# Sheet_1_2026-02-10.net
KiCad netlist of a schematic drawn in Altium Designer
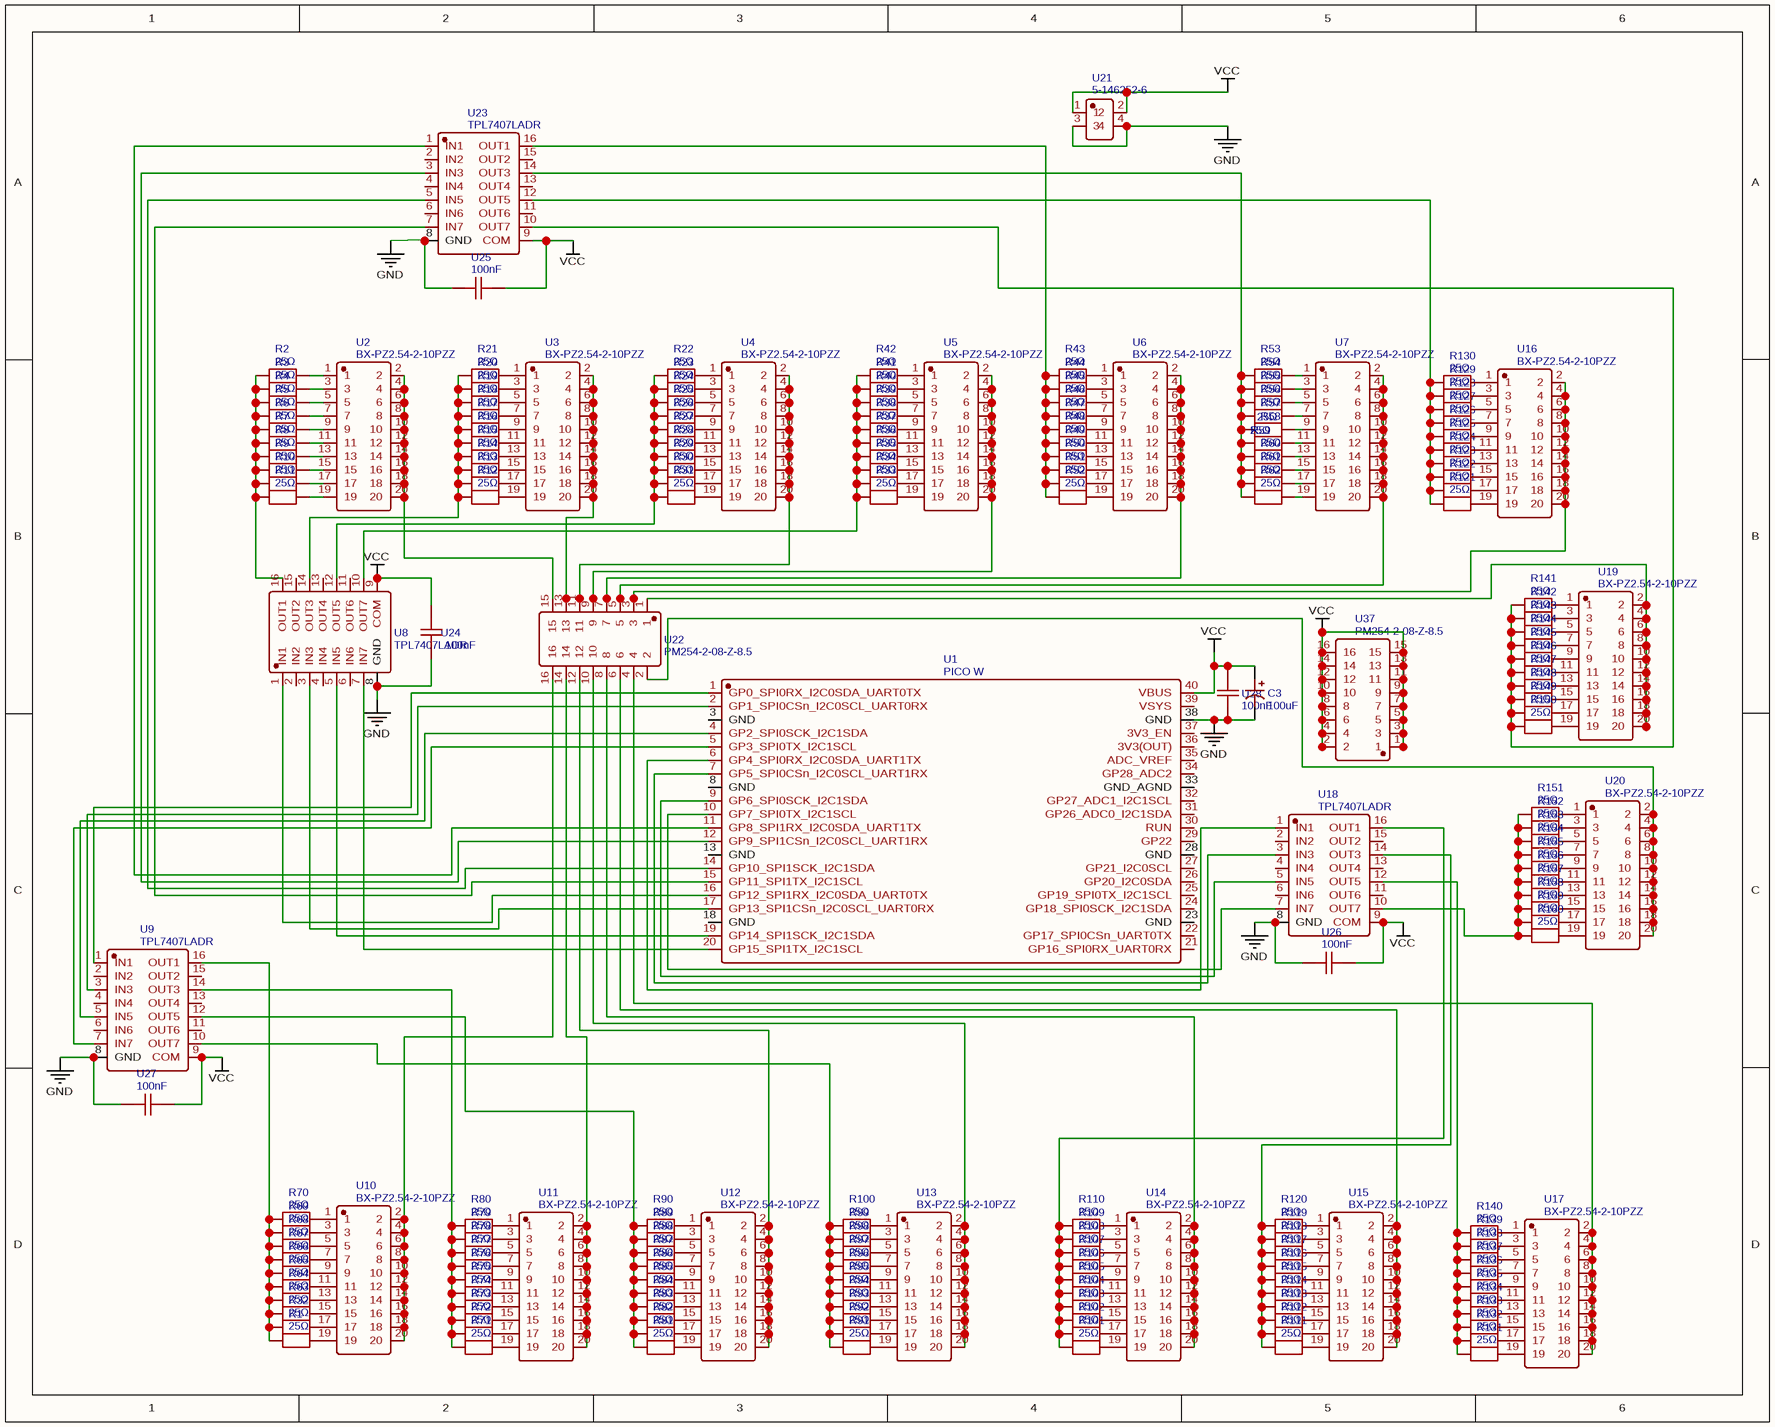
[diagram p0: Sheet_1_2026-02-10.schdoc]

(export (version "E")
  (design (tool "Eeschema 10.0.6"))
  (components
    (comp (ref "C3")
      (value "100uF")
      (fields
        (field (name "MANUFACTURER") "Econd(米朗电子)")
        (field (name "MANUFACTURER PART") "100uF25V6.3x11KM")
        (field (name "CONTRIBUTOR") "lcsc")
      )
      (libsource (lib "altium-import") (part "root_3_100uF_"))
    )
    (comp (ref "R1")
      (value "25Ω")
      (fields
        (field (name "MANUFACTURER") "YAGEO(国巨)")
        (field (name "MANUFACTURER PART") "RT0805BRD0725RL")
        (field (name "CONTRIBUTOR") "lcsc")
      )
      (libsource (lib "altium-import") (part "root_0_25Ω_"))
    )
    (comp (ref "R2")
      (value "25Ω")
      (fields
        (field (name "MANUFACTURER") "YAGEO(国巨)")
        (field (name "MANUFACTURER PART") "RT0805BRD0725RL")
        (field (name "CONTRIBUTOR") "lcsc")
      )
      (libsource (lib "altium-import") (part "root_0_25Ω_"))
    )
    (comp (ref "R3")
      (value "25Ω")
      (fields
        (field (name "MANUFACTURER") "YAGEO(国巨)")
        (field (name "MANUFACTURER PART") "RT0805BRD0725RL")
        (field (name "CONTRIBUTOR") "lcsc")
      )
      (libsource (lib "altium-import") (part "root_0_25Ω_"))
    )
    (comp (ref "R4")
      (value "25Ω")
      (fields
        (field (name "MANUFACTURER") "YAGEO(国巨)")
        (field (name "MANUFACTURER PART") "RT0805BRD0725RL")
        (field (name "CONTRIBUTOR") "lcsc")
      )
      (libsource (lib "altium-import") (part "root_0_25Ω_"))
    )
    (comp (ref "R5")
      (value "25Ω")
      (fields
        (field (name "MANUFACTURER") "YAGEO(国巨)")
        (field (name "MANUFACTURER PART") "RT0805BRD0725RL")
        (field (name "CONTRIBUTOR") "lcsc")
      )
      (libsource (lib "altium-import") (part "root_0_25Ω_"))
    )
    (comp (ref "R6")
      (value "25Ω")
      (fields
        (field (name "MANUFACTURER") "YAGEO(国巨)")
        (field (name "MANUFACTURER PART") "RT0805BRD0725RL")
        (field (name "CONTRIBUTOR") "lcsc")
      )
      (libsource (lib "altium-import") (part "root_0_25Ω_"))
    )
    (comp (ref "R7")
      (value "25Ω")
      (fields
        (field (name "MANUFACTURER") "YAGEO(国巨)")
        (field (name "MANUFACTURER PART") "RT0805BRD0725RL")
        (field (name "CONTRIBUTOR") "lcsc")
      )
      (libsource (lib "altium-import") (part "root_0_25Ω_"))
    )
    (comp (ref "R8")
      (value "25Ω")
      (fields
        (field (name "MANUFACTURER") "YAGEO(国巨)")
        (field (name "MANUFACTURER PART") "RT0805BRD0725RL")
        (field (name "CONTRIBUTOR") "lcsc")
      )
      (libsource (lib "altium-import") (part "root_0_25Ω_"))
    )
    (comp (ref "R9")
      (value "25Ω")
      (fields
        (field (name "MANUFACTURER") "YAGEO(国巨)")
        (field (name "MANUFACTURER PART") "RT0805BRD0725RL")
        (field (name "CONTRIBUTOR") "lcsc")
      )
      (libsource (lib "altium-import") (part "root_0_25Ω_"))
    )
    (comp (ref "R10")
      (value "25Ω")
      (fields
        (field (name "MANUFACTURER") "YAGEO(国巨)")
        (field (name "MANUFACTURER PART") "RT0805BRD0725RL")
        (field (name "CONTRIBUTOR") "lcsc")
      )
      (libsource (lib "altium-import") (part "root_0_25Ω_"))
    )
    (comp (ref "R11")
      (value "25Ω")
      (fields
        (field (name "MANUFACTURER") "YAGEO(国巨)")
        (field (name "MANUFACTURER PART") "RT0805BRD0725RL")
        (field (name "CONTRIBUTOR") "lcsc")
      )
      (libsource (lib "altium-import") (part "root_0_25Ω_"))
    )
    (comp (ref "R12")
      (value "25Ω")
      (fields
        (field (name "MANUFACTURER") "YAGEO(国巨)")
        (field (name "MANUFACTURER PART") "RT0805BRD0725RL")
        (field (name "CONTRIBUTOR") "lcsc")
      )
      (libsource (lib "altium-import") (part "root_0_25Ω_"))
    )
    (comp (ref "R13")
      (value "25Ω")
      (fields
        (field (name "MANUFACTURER") "YAGEO(国巨)")
        (field (name "MANUFACTURER PART") "RT0805BRD0725RL")
        (field (name "CONTRIBUTOR") "lcsc")
      )
      (libsource (lib "altium-import") (part "root_0_25Ω_"))
    )
    (comp (ref "R14")
      (value "25Ω")
      (fields
        (field (name "MANUFACTURER") "YAGEO(国巨)")
        (field (name "MANUFACTURER PART") "RT0805BRD0725RL")
        (field (name "CONTRIBUTOR") "lcsc")
      )
      (libsource (lib "altium-import") (part "root_0_25Ω_"))
    )
    (comp (ref "R15")
      (value "25Ω")
      (fields
        (field (name "MANUFACTURER") "YAGEO(国巨)")
        (field (name "MANUFACTURER PART") "RT0805BRD0725RL")
        (field (name "CONTRIBUTOR") "lcsc")
      )
      (libsource (lib "altium-import") (part "root_0_25Ω_"))
    )
    (comp (ref "R16")
      (value "25Ω")
      (fields
        (field (name "MANUFACTURER") "YAGEO(国巨)")
        (field (name "MANUFACTURER PART") "RT0805BRD0725RL")
        (field (name "CONTRIBUTOR") "lcsc")
      )
      (libsource (lib "altium-import") (part "root_0_25Ω_"))
    )
    (comp (ref "R17")
      (value "25Ω")
      (fields
        (field (name "MANUFACTURER") "YAGEO(国巨)")
        (field (name "MANUFACTURER PART") "RT0805BRD0725RL")
        (field (name "CONTRIBUTOR") "lcsc")
      )
      (libsource (lib "altium-import") (part "root_0_25Ω_"))
    )
    (comp (ref "R18")
      (value "25Ω")
      (fields
        (field (name "MANUFACTURER") "YAGEO(国巨)")
        (field (name "MANUFACTURER PART") "RT0805BRD0725RL")
        (field (name "CONTRIBUTOR") "lcsc")
      )
      (libsource (lib "altium-import") (part "root_0_25Ω_"))
    )
    (comp (ref "R19")
      (value "25Ω")
      (fields
        (field (name "MANUFACTURER") "YAGEO(国巨)")
        (field (name "MANUFACTURER PART") "RT0805BRD0725RL")
        (field (name "CONTRIBUTOR") "lcsc")
      )
      (libsource (lib "altium-import") (part "root_0_25Ω_"))
    )
    (comp (ref "R20")
      (value "25Ω")
      (fields
        (field (name "MANUFACTURER") "YAGEO(国巨)")
        (field (name "MANUFACTURER PART") "RT0805BRD0725RL")
        (field (name "CONTRIBUTOR") "lcsc")
      )
      (libsource (lib "altium-import") (part "root_0_25Ω_"))
    )
    (comp (ref "R21")
      (value "25Ω")
      (fields
        (field (name "MANUFACTURER") "YAGEO(国巨)")
        (field (name "MANUFACTURER PART") "RT0805BRD0725RL")
        (field (name "CONTRIBUTOR") "lcsc")
      )
      (libsource (lib "altium-import") (part "root_0_25Ω_"))
    )
    (comp (ref "R22")
      (value "25Ω")
      (fields
        (field (name "MANUFACTURER") "YAGEO(国巨)")
        (field (name "MANUFACTURER PART") "RT0805BRD0725RL")
        (field (name "CONTRIBUTOR") "lcsc")
      )
      (libsource (lib "altium-import") (part "root_0_25Ω_"))
    )
    (comp (ref "R23")
      (value "25Ω")
      (fields
        (field (name "MANUFACTURER") "YAGEO(国巨)")
        (field (name "MANUFACTURER PART") "RT0805BRD0725RL")
        (field (name "CONTRIBUTOR") "lcsc")
      )
      (libsource (lib "altium-import") (part "root_0_25Ω_"))
    )
    (comp (ref "R24")
      (value "25Ω")
      (fields
        (field (name "MANUFACTURER") "YAGEO(国巨)")
        (field (name "MANUFACTURER PART") "RT0805BRD0725RL")
        (field (name "CONTRIBUTOR") "lcsc")
      )
      (libsource (lib "altium-import") (part "root_0_25Ω_"))
    )
    (comp (ref "R25")
      (value "25Ω")
      (fields
        (field (name "MANUFACTURER") "YAGEO(国巨)")
        (field (name "MANUFACTURER PART") "RT0805BRD0725RL")
        (field (name "CONTRIBUTOR") "lcsc")
      )
      (libsource (lib "altium-import") (part "root_0_25Ω_"))
    )
    (comp (ref "R26")
      (value "25Ω")
      (fields
        (field (name "MANUFACTURER") "YAGEO(国巨)")
        (field (name "MANUFACTURER PART") "RT0805BRD0725RL")
        (field (name "CONTRIBUTOR") "lcsc")
      )
      (libsource (lib "altium-import") (part "root_0_25Ω_"))
    )
    (comp (ref "R27")
      (value "25Ω")
      (fields
        (field (name "MANUFACTURER") "YAGEO(国巨)")
        (field (name "MANUFACTURER PART") "RT0805BRD0725RL")
        (field (name "CONTRIBUTOR") "lcsc")
      )
      (libsource (lib "altium-import") (part "root_0_25Ω_"))
    )
    (comp (ref "R28")
      (value "25Ω")
      (fields
        (field (name "MANUFACTURER") "YAGEO(国巨)")
        (field (name "MANUFACTURER PART") "RT0805BRD0725RL")
        (field (name "CONTRIBUTOR") "lcsc")
      )
      (libsource (lib "altium-import") (part "root_0_25Ω_"))
    )
    (comp (ref "R29")
      (value "25Ω")
      (fields
        (field (name "MANUFACTURER") "YAGEO(国巨)")
        (field (name "MANUFACTURER PART") "RT0805BRD0725RL")
        (field (name "CONTRIBUTOR") "lcsc")
      )
      (libsource (lib "altium-import") (part "root_0_25Ω_"))
    )
    (comp (ref "R30")
      (value "25Ω")
      (fields
        (field (name "MANUFACTURER") "YAGEO(国巨)")
        (field (name "MANUFACTURER PART") "RT0805BRD0725RL")
        (field (name "CONTRIBUTOR") "lcsc")
      )
      (libsource (lib "altium-import") (part "root_0_25Ω_"))
    )
    (comp (ref "R31")
      (value "25Ω")
      (fields
        (field (name "MANUFACTURER") "YAGEO(国巨)")
        (field (name "MANUFACTURER PART") "RT0805BRD0725RL")
        (field (name "CONTRIBUTOR") "lcsc")
      )
      (libsource (lib "altium-import") (part "root_0_25Ω_"))
    )
    (comp (ref "R32")
      (value "25Ω")
      (fields
        (field (name "MANUFACTURER") "YAGEO(国巨)")
        (field (name "MANUFACTURER PART") "RT0805BRD0725RL")
        (field (name "CONTRIBUTOR") "lcsc")
      )
      (libsource (lib "altium-import") (part "root_0_25Ω_"))
    )
    (comp (ref "R33")
      (value "25Ω")
      (fields
        (field (name "MANUFACTURER") "YAGEO(国巨)")
        (field (name "MANUFACTURER PART") "RT0805BRD0725RL")
        (field (name "CONTRIBUTOR") "lcsc")
      )
      (libsource (lib "altium-import") (part "root_0_25Ω_"))
    )
    (comp (ref "R34")
      (value "25Ω")
      (fields
        (field (name "MANUFACTURER") "YAGEO(国巨)")
        (field (name "MANUFACTURER PART") "RT0805BRD0725RL")
        (field (name "CONTRIBUTOR") "lcsc")
      )
      (libsource (lib "altium-import") (part "root_0_25Ω_"))
    )
    (comp (ref "R35")
      (value "25Ω")
      (fields
        (field (name "MANUFACTURER") "YAGEO(国巨)")
        (field (name "MANUFACTURER PART") "RT0805BRD0725RL")
        (field (name "CONTRIBUTOR") "lcsc")
      )
      (libsource (lib "altium-import") (part "root_0_25Ω_"))
    )
    (comp (ref "R36")
      (value "25Ω")
      (fields
        (field (name "MANUFACTURER") "YAGEO(国巨)")
        (field (name "MANUFACTURER PART") "RT0805BRD0725RL")
        (field (name "CONTRIBUTOR") "lcsc")
      )
      (libsource (lib "altium-import") (part "root_0_25Ω_"))
    )
    (comp (ref "R37")
      (value "25Ω")
      (fields
        (field (name "MANUFACTURER") "YAGEO(国巨)")
        (field (name "MANUFACTURER PART") "RT0805BRD0725RL")
        (field (name "CONTRIBUTOR") "lcsc")
      )
      (libsource (lib "altium-import") (part "root_0_25Ω_"))
    )
    (comp (ref "R38")
      (value "25Ω")
      (fields
        (field (name "MANUFACTURER") "YAGEO(国巨)")
        (field (name "MANUFACTURER PART") "RT0805BRD0725RL")
        (field (name "CONTRIBUTOR") "lcsc")
      )
      (libsource (lib "altium-import") (part "root_0_25Ω_"))
    )
    (comp (ref "R39")
      (value "25Ω")
      (fields
        (field (name "MANUFACTURER") "YAGEO(国巨)")
        (field (name "MANUFACTURER PART") "RT0805BRD0725RL")
        (field (name "CONTRIBUTOR") "lcsc")
      )
      (libsource (lib "altium-import") (part "root_0_25Ω_"))
    )
    (comp (ref "R40")
      (value "25Ω")
      (fields
        (field (name "MANUFACTURER") "YAGEO(国巨)")
        (field (name "MANUFACTURER PART") "RT0805BRD0725RL")
        (field (name "CONTRIBUTOR") "lcsc")
      )
      (libsource (lib "altium-import") (part "root_0_25Ω_"))
    )
    (comp (ref "R41")
      (value "25Ω")
      (fields
        (field (name "MANUFACTURER") "YAGEO(国巨)")
        (field (name "MANUFACTURER PART") "RT0805BRD0725RL")
        (field (name "CONTRIBUTOR") "lcsc")
      )
      (libsource (lib "altium-import") (part "root_0_25Ω_"))
    )
    (comp (ref "R42")
      (value "25Ω")
      (fields
        (field (name "MANUFACTURER") "YAGEO(国巨)")
        (field (name "MANUFACTURER PART") "RT0805BRD0725RL")
        (field (name "CONTRIBUTOR") "lcsc")
      )
      (libsource (lib "altium-import") (part "root_0_25Ω_"))
    )
    (comp (ref "R43")
      (value "25Ω")
      (fields
        (field (name "MANUFACTURER") "YAGEO(国巨)")
        (field (name "MANUFACTURER PART") "RT0805BRD0725RL")
        (field (name "CONTRIBUTOR") "lcsc")
      )
      (libsource (lib "altium-import") (part "root_0_25Ω_"))
    )
    (comp (ref "R44")
      (value "25Ω")
      (fields
        (field (name "MANUFACTURER") "YAGEO(国巨)")
        (field (name "MANUFACTURER PART") "RT0805BRD0725RL")
        (field (name "CONTRIBUTOR") "lcsc")
      )
      (libsource (lib "altium-import") (part "root_0_25Ω_"))
    )
    (comp (ref "R45")
      (value "25Ω")
      (fields
        (field (name "MANUFACTURER") "YAGEO(国巨)")
        (field (name "MANUFACTURER PART") "RT0805BRD0725RL")
        (field (name "CONTRIBUTOR") "lcsc")
      )
      (libsource (lib "altium-import") (part "root_0_25Ω_"))
    )
    (comp (ref "R46")
      (value "25Ω")
      (fields
        (field (name "MANUFACTURER") "YAGEO(国巨)")
        (field (name "MANUFACTURER PART") "RT0805BRD0725RL")
        (field (name "CONTRIBUTOR") "lcsc")
      )
      (libsource (lib "altium-import") (part "root_0_25Ω_"))
    )
    (comp (ref "R47")
      (value "25Ω")
      (fields
        (field (name "MANUFACTURER") "YAGEO(国巨)")
        (field (name "MANUFACTURER PART") "RT0805BRD0725RL")
        (field (name "CONTRIBUTOR") "lcsc")
      )
      (libsource (lib "altium-import") (part "root_0_25Ω_"))
    )
    (comp (ref "R48")
      (value "25Ω")
      (fields
        (field (name "MANUFACTURER") "YAGEO(国巨)")
        (field (name "MANUFACTURER PART") "RT0805BRD0725RL")
        (field (name "CONTRIBUTOR") "lcsc")
      )
      (libsource (lib "altium-import") (part "root_0_25Ω_"))
    )
    (comp (ref "R49")
      (value "25Ω")
      (fields
        (field (name "MANUFACTURER") "YAGEO(国巨)")
        (field (name "MANUFACTURER PART") "RT0805BRD0725RL")
        (field (name "CONTRIBUTOR") "lcsc")
      )
      (libsource (lib "altium-import") (part "root_0_25Ω_"))
    )
    (comp (ref "R50")
      (value "25Ω")
      (fields
        (field (name "MANUFACTURER") "YAGEO(国巨)")
        (field (name "MANUFACTURER PART") "RT0805BRD0725RL")
        (field (name "CONTRIBUTOR") "lcsc")
      )
      (libsource (lib "altium-import") (part "root_0_25Ω_"))
    )
    (comp (ref "R51")
      (value "25Ω")
      (fields
        (field (name "MANUFACTURER") "YAGEO(国巨)")
        (field (name "MANUFACTURER PART") "RT0805BRD0725RL")
        (field (name "CONTRIBUTOR") "lcsc")
      )
      (libsource (lib "altium-import") (part "root_0_25Ω_"))
    )
    (comp (ref "R52")
      (value "25Ω")
      (fields
        (field (name "MANUFACTURER") "YAGEO(国巨)")
        (field (name "MANUFACTURER PART") "RT0805BRD0725RL")
        (field (name "CONTRIBUTOR") "lcsc")
      )
      (libsource (lib "altium-import") (part "root_0_25Ω_"))
    )
    (comp (ref "R53")
      (value "25Ω")
      (fields
        (field (name "MANUFACTURER") "YAGEO(国巨)")
        (field (name "MANUFACTURER PART") "RT0805BRD0725RL")
        (field (name "CONTRIBUTOR") "lcsc")
      )
      (libsource (lib "altium-import") (part "root_0_25Ω_"))
    )
    (comp (ref "R54")
      (value "25Ω")
      (fields
        (field (name "MANUFACTURER") "YAGEO(国巨)")
        (field (name "MANUFACTURER PART") "RT0805BRD0725RL")
        (field (name "CONTRIBUTOR") "lcsc")
      )
      (libsource (lib "altium-import") (part "root_0_25Ω_"))
    )
    (comp (ref "R55")
      (value "25Ω")
      (fields
        (field (name "MANUFACTURER") "YAGEO(国巨)")
        (field (name "MANUFACTURER PART") "RT0805BRD0725RL")
        (field (name "CONTRIBUTOR") "lcsc")
      )
      (libsource (lib "altium-import") (part "root_0_25Ω_"))
    )
    (comp (ref "R56")
      (value "25Ω")
      (fields
        (field (name "MANUFACTURER") "YAGEO(国巨)")
        (field (name "MANUFACTURER PART") "RT0805BRD0725RL")
        (field (name "CONTRIBUTOR") "lcsc")
      )
      (libsource (lib "altium-import") (part "root_0_25Ω_"))
    )
    (comp (ref "R57")
      (value "25Ω")
      (fields
        (field (name "MANUFACTURER") "YAGEO(国巨)")
        (field (name "MANUFACTURER PART") "RT0805BRD0725RL")
        (field (name "CONTRIBUTOR") "lcsc")
      )
      (libsource (lib "altium-import") (part "root_0_25Ω_"))
    )
    (comp (ref "R58")
      (value "25Ω")
      (fields
        (field (name "MANUFACTURER") "YAGEO(国巨)")
        (field (name "MANUFACTURER PART") "RT0805BRD0725RL")
        (field (name "CONTRIBUTOR") "lcsc")
      )
      (libsource (lib "altium-import") (part "root_0_25Ω_"))
    )
    (comp (ref "R59")
      (value "25Ω")
      (fields
        (field (name "MANUFACTURER") "YAGEO(国巨)")
        (field (name "MANUFACTURER PART") "RT0805BRD0725RL")
        (field (name "CONTRIBUTOR") "lcsc")
      )
      (libsource (lib "altium-import") (part "root_0_25Ω_"))
    )
    (comp (ref "R60")
      (value "25Ω")
      (fields
        (field (name "MANUFACTURER") "YAGEO(国巨)")
        (field (name "MANUFACTURER PART") "RT0805BRD0725RL")
        (field (name "CONTRIBUTOR") "lcsc")
      )
      (libsource (lib "altium-import") (part "root_0_25Ω_"))
    )
    (comp (ref "R61")
      (value "25Ω")
      (fields
        (field (name "MANUFACTURER") "YAGEO(国巨)")
        (field (name "MANUFACTURER PART") "RT0805BRD0725RL")
        (field (name "CONTRIBUTOR") "lcsc")
      )
      (libsource (lib "altium-import") (part "root_0_25Ω_"))
    )
    (comp (ref "R62")
      (value "25Ω")
      (fields
        (field (name "MANUFACTURER") "YAGEO(国巨)")
        (field (name "MANUFACTURER PART") "RT0805BRD0725RL")
        (field (name "CONTRIBUTOR") "lcsc")
      )
      (libsource (lib "altium-import") (part "root_0_25Ω_"))
    )
    (comp (ref "R63")
      (value "25Ω")
      (fields
        (field (name "MANUFACTURER") "YAGEO(国巨)")
        (field (name "MANUFACTURER PART") "RT0805BRD0725RL")
        (field (name "CONTRIBUTOR") "lcsc")
      )
      (libsource (lib "altium-import") (part "root_0_25Ω_"))
    )
    (comp (ref "R64")
      (value "25Ω")
      (fields
        (field (name "MANUFACTURER") "YAGEO(国巨)")
        (field (name "MANUFACTURER PART") "RT0805BRD0725RL")
        (field (name "CONTRIBUTOR") "lcsc")
      )
      (libsource (lib "altium-import") (part "root_0_25Ω_"))
    )
    (comp (ref "R65")
      (value "25Ω")
      (fields
        (field (name "MANUFACTURER") "YAGEO(国巨)")
        (field (name "MANUFACTURER PART") "RT0805BRD0725RL")
        (field (name "CONTRIBUTOR") "lcsc")
      )
      (libsource (lib "altium-import") (part "root_0_25Ω_"))
    )
    (comp (ref "R66")
      (value "25Ω")
      (fields
        (field (name "MANUFACTURER") "YAGEO(国巨)")
        (field (name "MANUFACTURER PART") "RT0805BRD0725RL")
        (field (name "CONTRIBUTOR") "lcsc")
      )
      (libsource (lib "altium-import") (part "root_0_25Ω_"))
    )
    (comp (ref "R67")
      (value "25Ω")
      (fields
        (field (name "MANUFACTURER") "YAGEO(国巨)")
        (field (name "MANUFACTURER PART") "RT0805BRD0725RL")
        (field (name "CONTRIBUTOR") "lcsc")
      )
      (libsource (lib "altium-import") (part "root_0_25Ω_"))
    )
    (comp (ref "R68")
      (value "25Ω")
      (fields
        (field (name "MANUFACTURER") "YAGEO(国巨)")
        (field (name "MANUFACTURER PART") "RT0805BRD0725RL")
        (field (name "CONTRIBUTOR") "lcsc")
      )
      (libsource (lib "altium-import") (part "root_0_25Ω_"))
    )
    (comp (ref "R69")
      (value "25Ω")
      (fields
        (field (name "MANUFACTURER") "YAGEO(国巨)")
        (field (name "MANUFACTURER PART") "RT0805BRD0725RL")
        (field (name "CONTRIBUTOR") "lcsc")
      )
      (libsource (lib "altium-import") (part "root_0_25Ω_"))
    )
    (comp (ref "R70")
      (value "25Ω")
      (fields
        (field (name "MANUFACTURER") "YAGEO(国巨)")
        (field (name "MANUFACTURER PART") "RT0805BRD0725RL")
        (field (name "CONTRIBUTOR") "lcsc")
      )
      (libsource (lib "altium-import") (part "root_0_25Ω_"))
    )
    (comp (ref "R71")
      (value "25Ω")
      (fields
        (field (name "MANUFACTURER") "YAGEO(国巨)")
        (field (name "MANUFACTURER PART") "RT0805BRD0725RL")
        (field (name "CONTRIBUTOR") "lcsc")
      )
      (libsource (lib "altium-import") (part "root_0_25Ω_"))
    )
    (comp (ref "R72")
      (value "25Ω")
      (fields
        (field (name "MANUFACTURER") "YAGEO(国巨)")
        (field (name "MANUFACTURER PART") "RT0805BRD0725RL")
        (field (name "CONTRIBUTOR") "lcsc")
      )
      (libsource (lib "altium-import") (part "root_0_25Ω_"))
    )
    (comp (ref "R73")
      (value "25Ω")
      (fields
        (field (name "MANUFACTURER") "YAGEO(国巨)")
        (field (name "MANUFACTURER PART") "RT0805BRD0725RL")
        (field (name "CONTRIBUTOR") "lcsc")
      )
      (libsource (lib "altium-import") (part "root_0_25Ω_"))
    )
    (comp (ref "R74")
      (value "25Ω")
      (fields
        (field (name "MANUFACTURER") "YAGEO(国巨)")
        (field (name "MANUFACTURER PART") "RT0805BRD0725RL")
        (field (name "CONTRIBUTOR") "lcsc")
      )
      (libsource (lib "altium-import") (part "root_0_25Ω_"))
    )
    (comp (ref "R75")
      (value "25Ω")
      (fields
        (field (name "MANUFACTURER") "YAGEO(国巨)")
        (field (name "MANUFACTURER PART") "RT0805BRD0725RL")
        (field (name "CONTRIBUTOR") "lcsc")
      )
      (libsource (lib "altium-import") (part "root_0_25Ω_"))
    )
    (comp (ref "R76")
      (value "25Ω")
      (fields
        (field (name "MANUFACTURER") "YAGEO(国巨)")
        (field (name "MANUFACTURER PART") "RT0805BRD0725RL")
        (field (name "CONTRIBUTOR") "lcsc")
      )
      (libsource (lib "altium-import") (part "root_0_25Ω_"))
    )
    (comp (ref "R77")
      (value "25Ω")
      (fields
        (field (name "MANUFACTURER") "YAGEO(国巨)")
        (field (name "MANUFACTURER PART") "RT0805BRD0725RL")
        (field (name "CONTRIBUTOR") "lcsc")
      )
      (libsource (lib "altium-import") (part "root_0_25Ω_"))
    )
    (comp (ref "R78")
      (value "25Ω")
      (fields
        (field (name "MANUFACTURER") "YAGEO(国巨)")
        (field (name "MANUFACTURER PART") "RT0805BRD0725RL")
        (field (name "CONTRIBUTOR") "lcsc")
      )
      (libsource (lib "altium-import") (part "root_0_25Ω_"))
    )
    (comp (ref "R79")
      (value "25Ω")
      (fields
        (field (name "MANUFACTURER") "YAGEO(国巨)")
        (field (name "MANUFACTURER PART") "RT0805BRD0725RL")
        (field (name "CONTRIBUTOR") "lcsc")
      )
      (libsource (lib "altium-import") (part "root_0_25Ω_"))
    )
    (comp (ref "R80")
      (value "25Ω")
      (fields
        (field (name "MANUFACTURER") "YAGEO(国巨)")
        (field (name "MANUFACTURER PART") "RT0805BRD0725RL")
        (field (name "CONTRIBUTOR") "lcsc")
      )
      (libsource (lib "altium-import") (part "root_0_25Ω_"))
    )
    (comp (ref "R81")
      (value "25Ω")
      (fields
        (field (name "MANUFACTURER") "YAGEO(国巨)")
        (field (name "MANUFACTURER PART") "RT0805BRD0725RL")
        (field (name "CONTRIBUTOR") "lcsc")
      )
      (libsource (lib "altium-import") (part "root_0_25Ω_"))
    )
    (comp (ref "R82")
      (value "25Ω")
      (fields
        (field (name "MANUFACTURER") "YAGEO(国巨)")
        (field (name "MANUFACTURER PART") "RT0805BRD0725RL")
        (field (name "CONTRIBUTOR") "lcsc")
      )
      (libsource (lib "altium-import") (part "root_0_25Ω_"))
    )
    (comp (ref "R83")
      (value "25Ω")
      (fields
        (field (name "MANUFACTURER") "YAGEO(国巨)")
        (field (name "MANUFACTURER PART") "RT0805BRD0725RL")
        (field (name "CONTRIBUTOR") "lcsc")
      )
      (libsource (lib "altium-import") (part "root_0_25Ω_"))
    )
    (comp (ref "R84")
      (value "25Ω")
      (fields
        (field (name "MANUFACTURER") "YAGEO(国巨)")
        (field (name "MANUFACTURER PART") "RT0805BRD0725RL")
        (field (name "CONTRIBUTOR") "lcsc")
      )
      (libsource (lib "altium-import") (part "root_0_25Ω_"))
    )
    (comp (ref "R85")
      (value "25Ω")
      (fields
        (field (name "MANUFACTURER") "YAGEO(国巨)")
        (field (name "MANUFACTURER PART") "RT0805BRD0725RL")
        (field (name "CONTRIBUTOR") "lcsc")
      )
      (libsource (lib "altium-import") (part "root_0_25Ω_"))
    )
    (comp (ref "R86")
      (value "25Ω")
      (fields
        (field (name "MANUFACTURER") "YAGEO(国巨)")
        (field (name "MANUFACTURER PART") "RT0805BRD0725RL")
        (field (name "CONTRIBUTOR") "lcsc")
      )
      (libsource (lib "altium-import") (part "root_0_25Ω_"))
    )
    (comp (ref "R87")
      (value "25Ω")
      (fields
        (field (name "MANUFACTURER") "YAGEO(国巨)")
        (field (name "MANUFACTURER PART") "RT0805BRD0725RL")
        (field (name "CONTRIBUTOR") "lcsc")
      )
      (libsource (lib "altium-import") (part "root_0_25Ω_"))
    )
    (comp (ref "R88")
      (value "25Ω")
      (fields
        (field (name "MANUFACTURER") "YAGEO(国巨)")
        (field (name "MANUFACTURER PART") "RT0805BRD0725RL")
        (field (name "CONTRIBUTOR") "lcsc")
      )
      (libsource (lib "altium-import") (part "root_0_25Ω_"))
    )
    (comp (ref "R89")
      (value "25Ω")
      (fields
        (field (name "MANUFACTURER") "YAGEO(国巨)")
        (field (name "MANUFACTURER PART") "RT0805BRD0725RL")
        (field (name "CONTRIBUTOR") "lcsc")
      )
      (libsource (lib "altium-import") (part "root_0_25Ω_"))
    )
    (comp (ref "R90")
      (value "25Ω")
      (fields
        (field (name "MANUFACTURER") "YAGEO(国巨)")
        (field (name "MANUFACTURER PART") "RT0805BRD0725RL")
        (field (name "CONTRIBUTOR") "lcsc")
      )
      (libsource (lib "altium-import") (part "root_0_25Ω_"))
    )
    (comp (ref "R91")
      (value "25Ω")
      (fields
        (field (name "MANUFACTURER") "YAGEO(国巨)")
        (field (name "MANUFACTURER PART") "RT0805BRD0725RL")
        (field (name "CONTRIBUTOR") "lcsc")
      )
      (libsource (lib "altium-import") (part "root_0_25Ω_"))
    )
    (comp (ref "R92")
      (value "25Ω")
      (fields
        (field (name "MANUFACTURER") "YAGEO(国巨)")
        (field (name "MANUFACTURER PART") "RT0805BRD0725RL")
        (field (name "CONTRIBUTOR") "lcsc")
      )
      (libsource (lib "altium-import") (part "root_0_25Ω_"))
    )
    (comp (ref "R93")
      (value "25Ω")
      (fields
        (field (name "MANUFACTURER") "YAGEO(国巨)")
        (field (name "MANUFACTURER PART") "RT0805BRD0725RL")
        (field (name "CONTRIBUTOR") "lcsc")
      )
      (libsource (lib "altium-import") (part "root_0_25Ω_"))
    )
    (comp (ref "R94")
      (value "25Ω")
      (fields
        (field (name "MANUFACTURER") "YAGEO(国巨)")
        (field (name "MANUFACTURER PART") "RT0805BRD0725RL")
        (field (name "CONTRIBUTOR") "lcsc")
      )
      (libsource (lib "altium-import") (part "root_0_25Ω_"))
    )
    (comp (ref "R95")
      (value "25Ω")
      (fields
        (field (name "MANUFACTURER") "YAGEO(国巨)")
        (field (name "MANUFACTURER PART") "RT0805BRD0725RL")
        (field (name "CONTRIBUTOR") "lcsc")
      )
      (libsource (lib "altium-import") (part "root_0_25Ω_"))
    )
    (comp (ref "R96")
      (value "25Ω")
      (fields
        (field (name "MANUFACTURER") "YAGEO(国巨)")
        (field (name "MANUFACTURER PART") "RT0805BRD0725RL")
        (field (name "CONTRIBUTOR") "lcsc")
      )
      (libsource (lib "altium-import") (part "root_0_25Ω_"))
    )
    (comp (ref "R97")
      (value "25Ω")
      (fields
        (field (name "MANUFACTURER") "YAGEO(国巨)")
        (field (name "MANUFACTURER PART") "RT0805BRD0725RL")
        (field (name "CONTRIBUTOR") "lcsc")
      )
      (libsource (lib "altium-import") (part "root_0_25Ω_"))
    )
    (comp (ref "R98")
      (value "25Ω")
      (fields
        (field (name "MANUFACTURER") "YAGEO(国巨)")
        (field (name "MANUFACTURER PART") "RT0805BRD0725RL")
        (field (name "CONTRIBUTOR") "lcsc")
      )
      (libsource (lib "altium-import") (part "root_0_25Ω_"))
    )
    (comp (ref "R99")
      (value "25Ω")
      (fields
        (field (name "MANUFACTURER") "YAGEO(国巨)")
        (field (name "MANUFACTURER PART") "RT0805BRD0725RL")
        (field (name "CONTRIBUTOR") "lcsc")
      )
      (libsource (lib "altium-import") (part "root_0_25Ω_"))
    )
    (comp (ref "R100")
      (value "25Ω")
      (fields
        (field (name "MANUFACTURER") "YAGEO(国巨)")
        (field (name "MANUFACTURER PART") "RT0805BRD0725RL")
        (field (name "CONTRIBUTOR") "lcsc")
      )
      (libsource (lib "altium-import") (part "root_0_25Ω_"))
    )
    (comp (ref "R101")
      (value "25Ω")
      (fields
        (field (name "MANUFACTURER") "YAGEO(国巨)")
        (field (name "MANUFACTURER PART") "RT0805BRD0725RL")
        (field (name "CONTRIBUTOR") "lcsc")
      )
      (libsource (lib "altium-import") (part "root_0_25Ω_"))
    )
    (comp (ref "R102")
      (value "25Ω")
      (fields
        (field (name "MANUFACTURER") "YAGEO(国巨)")
        (field (name "MANUFACTURER PART") "RT0805BRD0725RL")
        (field (name "CONTRIBUTOR") "lcsc")
      )
      (libsource (lib "altium-import") (part "root_0_25Ω_"))
    )
    (comp (ref "R103")
      (value "25Ω")
      (fields
        (field (name "MANUFACTURER") "YAGEO(国巨)")
        (field (name "MANUFACTURER PART") "RT0805BRD0725RL")
        (field (name "CONTRIBUTOR") "lcsc")
      )
      (libsource (lib "altium-import") (part "root_0_25Ω_"))
    )
    (comp (ref "R104")
      (value "25Ω")
      (fields
        (field (name "MANUFACTURER") "YAGEO(国巨)")
        (field (name "MANUFACTURER PART") "RT0805BRD0725RL")
        (field (name "CONTRIBUTOR") "lcsc")
      )
      (libsource (lib "altium-import") (part "root_0_25Ω_"))
    )
    (comp (ref "R105")
      (value "25Ω")
      (fields
        (field (name "MANUFACTURER") "YAGEO(国巨)")
        (field (name "MANUFACTURER PART") "RT0805BRD0725RL")
        (field (name "CONTRIBUTOR") "lcsc")
      )
      (libsource (lib "altium-import") (part "root_0_25Ω_"))
    )
    (comp (ref "R106")
      (value "25Ω")
      (fields
        (field (name "MANUFACTURER") "YAGEO(国巨)")
        (field (name "MANUFACTURER PART") "RT0805BRD0725RL")
        (field (name "CONTRIBUTOR") "lcsc")
      )
      (libsource (lib "altium-import") (part "root_0_25Ω_"))
    )
    (comp (ref "R107")
      (value "25Ω")
      (fields
        (field (name "MANUFACTURER") "YAGEO(国巨)")
        (field (name "MANUFACTURER PART") "RT0805BRD0725RL")
        (field (name "CONTRIBUTOR") "lcsc")
      )
      (libsource (lib "altium-import") (part "root_0_25Ω_"))
    )
    (comp (ref "R108")
      (value "25Ω")
      (fields
        (field (name "MANUFACTURER") "YAGEO(国巨)")
        (field (name "MANUFACTURER PART") "RT0805BRD0725RL")
        (field (name "CONTRIBUTOR") "lcsc")
      )
      (libsource (lib "altium-import") (part "root_0_25Ω_"))
    )
    (comp (ref "R109")
      (value "25Ω")
      (fields
        (field (name "MANUFACTURER") "YAGEO(国巨)")
        (field (name "MANUFACTURER PART") "RT0805BRD0725RL")
        (field (name "CONTRIBUTOR") "lcsc")
      )
      (libsource (lib "altium-import") (part "root_0_25Ω_"))
    )
    (comp (ref "R110")
      (value "25Ω")
      (fields
        (field (name "MANUFACTURER") "YAGEO(国巨)")
        (field (name "MANUFACTURER PART") "RT0805BRD0725RL")
        (field (name "CONTRIBUTOR") "lcsc")
      )
      (libsource (lib "altium-import") (part "root_0_25Ω_"))
    )
    (comp (ref "R111")
      (value "25Ω")
      (fields
        (field (name "MANUFACTURER") "YAGEO(国巨)")
        (field (name "MANUFACTURER PART") "RT0805BRD0725RL")
        (field (name "CONTRIBUTOR") "lcsc")
      )
      (libsource (lib "altium-import") (part "root_0_25Ω_"))
    )
    (comp (ref "R112")
      (value "25Ω")
      (fields
        (field (name "MANUFACTURER") "YAGEO(国巨)")
        (field (name "MANUFACTURER PART") "RT0805BRD0725RL")
        (field (name "CONTRIBUTOR") "lcsc")
      )
      (libsource (lib "altium-import") (part "root_0_25Ω_"))
    )
    (comp (ref "R113")
      (value "25Ω")
      (fields
        (field (name "MANUFACTURER") "YAGEO(国巨)")
        (field (name "MANUFACTURER PART") "RT0805BRD0725RL")
        (field (name "CONTRIBUTOR") "lcsc")
      )
      (libsource (lib "altium-import") (part "root_0_25Ω_"))
    )
    (comp (ref "R114")
      (value "25Ω")
      (fields
        (field (name "MANUFACTURER") "YAGEO(国巨)")
        (field (name "MANUFACTURER PART") "RT0805BRD0725RL")
        (field (name "CONTRIBUTOR") "lcsc")
      )
      (libsource (lib "altium-import") (part "root_0_25Ω_"))
    )
    (comp (ref "R115")
      (value "25Ω")
      (fields
        (field (name "MANUFACTURER") "YAGEO(国巨)")
        (field (name "MANUFACTURER PART") "RT0805BRD0725RL")
        (field (name "CONTRIBUTOR") "lcsc")
      )
      (libsource (lib "altium-import") (part "root_0_25Ω_"))
    )
    (comp (ref "R116")
      (value "25Ω")
      (fields
        (field (name "MANUFACTURER") "YAGEO(国巨)")
        (field (name "MANUFACTURER PART") "RT0805BRD0725RL")
        (field (name "CONTRIBUTOR") "lcsc")
      )
      (libsource (lib "altium-import") (part "root_0_25Ω_"))
    )
    (comp (ref "R117")
      (value "25Ω")
      (fields
        (field (name "MANUFACTURER") "YAGEO(国巨)")
        (field (name "MANUFACTURER PART") "RT0805BRD0725RL")
        (field (name "CONTRIBUTOR") "lcsc")
      )
      (libsource (lib "altium-import") (part "root_0_25Ω_"))
    )
    (comp (ref "R118")
      (value "25Ω")
      (fields
        (field (name "MANUFACTURER") "YAGEO(国巨)")
        (field (name "MANUFACTURER PART") "RT0805BRD0725RL")
        (field (name "CONTRIBUTOR") "lcsc")
      )
      (libsource (lib "altium-import") (part "root_0_25Ω_"))
    )
    (comp (ref "R119")
      (value "25Ω")
      (fields
        (field (name "MANUFACTURER") "YAGEO(国巨)")
        (field (name "MANUFACTURER PART") "RT0805BRD0725RL")
        (field (name "CONTRIBUTOR") "lcsc")
      )
      (libsource (lib "altium-import") (part "root_0_25Ω_"))
    )
    (comp (ref "R120")
      (value "25Ω")
      (fields
        (field (name "MANUFACTURER") "YAGEO(国巨)")
        (field (name "MANUFACTURER PART") "RT0805BRD0725RL")
        (field (name "CONTRIBUTOR") "lcsc")
      )
      (libsource (lib "altium-import") (part "root_0_25Ω_"))
    )
    (comp (ref "R121")
      (value "25Ω")
      (fields
        (field (name "MANUFACTURER") "YAGEO(国巨)")
        (field (name "MANUFACTURER PART") "RT0805BRD0725RL")
        (field (name "CONTRIBUTOR") "lcsc")
      )
      (libsource (lib "altium-import") (part "root_0_25Ω_"))
    )
    (comp (ref "R122")
      (value "25Ω")
      (fields
        (field (name "MANUFACTURER") "YAGEO(国巨)")
        (field (name "MANUFACTURER PART") "RT0805BRD0725RL")
        (field (name "CONTRIBUTOR") "lcsc")
      )
      (libsource (lib "altium-import") (part "root_0_25Ω_"))
    )
    (comp (ref "R123")
      (value "25Ω")
      (fields
        (field (name "MANUFACTURER") "YAGEO(国巨)")
        (field (name "MANUFACTURER PART") "RT0805BRD0725RL")
        (field (name "CONTRIBUTOR") "lcsc")
      )
      (libsource (lib "altium-import") (part "root_0_25Ω_"))
    )
    (comp (ref "R124")
      (value "25Ω")
      (fields
        (field (name "MANUFACTURER") "YAGEO(国巨)")
        (field (name "MANUFACTURER PART") "RT0805BRD0725RL")
        (field (name "CONTRIBUTOR") "lcsc")
      )
      (libsource (lib "altium-import") (part "root_0_25Ω_"))
    )
    (comp (ref "R125")
      (value "25Ω")
      (fields
        (field (name "MANUFACTURER") "YAGEO(国巨)")
        (field (name "MANUFACTURER PART") "RT0805BRD0725RL")
        (field (name "CONTRIBUTOR") "lcsc")
      )
      (libsource (lib "altium-import") (part "root_0_25Ω_"))
    )
    (comp (ref "R126")
      (value "25Ω")
      (fields
        (field (name "MANUFACTURER") "YAGEO(国巨)")
        (field (name "MANUFACTURER PART") "RT0805BRD0725RL")
        (field (name "CONTRIBUTOR") "lcsc")
      )
      (libsource (lib "altium-import") (part "root_0_25Ω_"))
    )
    (comp (ref "R127")
      (value "25Ω")
      (fields
        (field (name "MANUFACTURER") "YAGEO(国巨)")
        (field (name "MANUFACTURER PART") "RT0805BRD0725RL")
        (field (name "CONTRIBUTOR") "lcsc")
      )
      (libsource (lib "altium-import") (part "root_0_25Ω_"))
    )
    (comp (ref "R128")
      (value "25Ω")
      (fields
        (field (name "MANUFACTURER") "YAGEO(国巨)")
        (field (name "MANUFACTURER PART") "RT0805BRD0725RL")
        (field (name "CONTRIBUTOR") "lcsc")
      )
      (libsource (lib "altium-import") (part "root_0_25Ω_"))
    )
    (comp (ref "R129")
      (value "25Ω")
      (fields
        (field (name "MANUFACTURER") "YAGEO(国巨)")
        (field (name "MANUFACTURER PART") "RT0805BRD0725RL")
        (field (name "CONTRIBUTOR") "lcsc")
      )
      (libsource (lib "altium-import") (part "root_0_25Ω_"))
    )
    (comp (ref "R130")
      (value "25Ω")
      (fields
        (field (name "MANUFACTURER") "YAGEO(国巨)")
        (field (name "MANUFACTURER PART") "RT0805BRD0725RL")
        (field (name "CONTRIBUTOR") "lcsc")
      )
      (libsource (lib "altium-import") (part "root_0_25Ω_"))
    )
    (comp (ref "R131")
      (value "25Ω")
      (fields
        (field (name "MANUFACTURER") "YAGEO(国巨)")
        (field (name "MANUFACTURER PART") "RT0805BRD0725RL")
        (field (name "CONTRIBUTOR") "lcsc")
      )
      (libsource (lib "altium-import") (part "root_0_25Ω_"))
    )
    (comp (ref "R132")
      (value "25Ω")
      (fields
        (field (name "MANUFACTURER") "YAGEO(国巨)")
        (field (name "MANUFACTURER PART") "RT0805BRD0725RL")
        (field (name "CONTRIBUTOR") "lcsc")
      )
      (libsource (lib "altium-import") (part "root_0_25Ω_"))
    )
    (comp (ref "R133")
      (value "25Ω")
      (fields
        (field (name "MANUFACTURER") "YAGEO(国巨)")
        (field (name "MANUFACTURER PART") "RT0805BRD0725RL")
        (field (name "CONTRIBUTOR") "lcsc")
      )
      (libsource (lib "altium-import") (part "root_0_25Ω_"))
    )
    (comp (ref "R134")
      (value "25Ω")
      (fields
        (field (name "MANUFACTURER") "YAGEO(国巨)")
        (field (name "MANUFACTURER PART") "RT0805BRD0725RL")
        (field (name "CONTRIBUTOR") "lcsc")
      )
      (libsource (lib "altium-import") (part "root_0_25Ω_"))
    )
    (comp (ref "R135")
      (value "25Ω")
      (fields
        (field (name "MANUFACTURER") "YAGEO(国巨)")
        (field (name "MANUFACTURER PART") "RT0805BRD0725RL")
        (field (name "CONTRIBUTOR") "lcsc")
      )
      (libsource (lib "altium-import") (part "root_0_25Ω_"))
    )
    (comp (ref "R136")
      (value "25Ω")
      (fields
        (field (name "MANUFACTURER") "YAGEO(国巨)")
        (field (name "MANUFACTURER PART") "RT0805BRD0725RL")
        (field (name "CONTRIBUTOR") "lcsc")
      )
      (libsource (lib "altium-import") (part "root_0_25Ω_"))
    )
    (comp (ref "R137")
      (value "25Ω")
      (fields
        (field (name "MANUFACTURER") "YAGEO(国巨)")
        (field (name "MANUFACTURER PART") "RT0805BRD0725RL")
        (field (name "CONTRIBUTOR") "lcsc")
      )
      (libsource (lib "altium-import") (part "root_0_25Ω_"))
    )
    (comp (ref "R138")
      (value "25Ω")
      (fields
        (field (name "MANUFACTURER") "YAGEO(国巨)")
        (field (name "MANUFACTURER PART") "RT0805BRD0725RL")
        (field (name "CONTRIBUTOR") "lcsc")
      )
      (libsource (lib "altium-import") (part "root_0_25Ω_"))
    )
    (comp (ref "R139")
      (value "25Ω")
      (fields
        (field (name "MANUFACTURER") "YAGEO(国巨)")
        (field (name "MANUFACTURER PART") "RT0805BRD0725RL")
        (field (name "CONTRIBUTOR") "lcsc")
      )
      (libsource (lib "altium-import") (part "root_0_25Ω_"))
    )
    (comp (ref "R140")
      (value "25Ω")
      (fields
        (field (name "MANUFACTURER") "YAGEO(国巨)")
        (field (name "MANUFACTURER PART") "RT0805BRD0725RL")
        (field (name "CONTRIBUTOR") "lcsc")
      )
      (libsource (lib "altium-import") (part "root_0_25Ω_"))
    )
    (comp (ref "R141")
      (value "25Ω")
      (fields
        (field (name "MANUFACTURER") "YAGEO(国巨)")
        (field (name "MANUFACTURER PART") "RT0805BRD0725RL")
        (field (name "CONTRIBUTOR") "lcsc")
      )
      (libsource (lib "altium-import") (part "root_0_25Ω_"))
    )
    (comp (ref "R142")
      (value "25Ω")
      (fields
        (field (name "MANUFACTURER") "YAGEO(国巨)")
        (field (name "MANUFACTURER PART") "RT0805BRD0725RL")
        (field (name "CONTRIBUTOR") "lcsc")
      )
      (libsource (lib "altium-import") (part "root_0_25Ω_"))
    )
    (comp (ref "R143")
      (value "25Ω")
      (fields
        (field (name "MANUFACTURER") "YAGEO(国巨)")
        (field (name "MANUFACTURER PART") "RT0805BRD0725RL")
        (field (name "CONTRIBUTOR") "lcsc")
      )
      (libsource (lib "altium-import") (part "root_0_25Ω_"))
    )
    (comp (ref "R144")
      (value "25Ω")
      (fields
        (field (name "MANUFACTURER") "YAGEO(国巨)")
        (field (name "MANUFACTURER PART") "RT0805BRD0725RL")
        (field (name "CONTRIBUTOR") "lcsc")
      )
      (libsource (lib "altium-import") (part "root_0_25Ω_"))
    )
    (comp (ref "R145")
      (value "25Ω")
      (fields
        (field (name "MANUFACTURER") "YAGEO(国巨)")
        (field (name "MANUFACTURER PART") "RT0805BRD0725RL")
        (field (name "CONTRIBUTOR") "lcsc")
      )
      (libsource (lib "altium-import") (part "root_0_25Ω_"))
    )
    (comp (ref "R146")
      (value "25Ω")
      (fields
        (field (name "MANUFACTURER") "YAGEO(国巨)")
        (field (name "MANUFACTURER PART") "RT0805BRD0725RL")
        (field (name "CONTRIBUTOR") "lcsc")
      )
      (libsource (lib "altium-import") (part "root_0_25Ω_"))
    )
    (comp (ref "R147")
      (value "25Ω")
      (fields
        (field (name "MANUFACTURER") "YAGEO(国巨)")
        (field (name "MANUFACTURER PART") "RT0805BRD0725RL")
        (field (name "CONTRIBUTOR") "lcsc")
      )
      (libsource (lib "altium-import") (part "root_0_25Ω_"))
    )
    (comp (ref "R148")
      (value "25Ω")
      (fields
        (field (name "MANUFACTURER") "YAGEO(国巨)")
        (field (name "MANUFACTURER PART") "RT0805BRD0725RL")
        (field (name "CONTRIBUTOR") "lcsc")
      )
      (libsource (lib "altium-import") (part "root_0_25Ω_"))
    )
    (comp (ref "R149")
      (value "25Ω")
      (fields
        (field (name "MANUFACTURER") "YAGEO(国巨)")
        (field (name "MANUFACTURER PART") "RT0805BRD0725RL")
        (field (name "CONTRIBUTOR") "lcsc")
      )
      (libsource (lib "altium-import") (part "root_0_25Ω_"))
    )
    (comp (ref "R150")
      (value "25Ω")
      (fields
        (field (name "MANUFACTURER") "YAGEO(国巨)")
        (field (name "MANUFACTURER PART") "RT0805BRD0725RL")
        (field (name "CONTRIBUTOR") "lcsc")
      )
      (libsource (lib "altium-import") (part "root_0_25Ω_"))
    )
    (comp (ref "R151")
      (value "25Ω")
      (fields
        (field (name "MANUFACTURER") "YAGEO(国巨)")
        (field (name "MANUFACTURER PART") "RT0805BRD0725RL")
        (field (name "CONTRIBUTOR") "lcsc")
      )
      (libsource (lib "altium-import") (part "root_0_25Ω_"))
    )
    (comp (ref "R152")
      (value "25Ω")
      (fields
        (field (name "MANUFACTURER") "YAGEO(国巨)")
        (field (name "MANUFACTURER PART") "RT0805BRD0725RL")
        (field (name "CONTRIBUTOR") "lcsc")
      )
      (libsource (lib "altium-import") (part "root_0_25Ω_"))
    )
    (comp (ref "R153")
      (value "25Ω")
      (fields
        (field (name "MANUFACTURER") "YAGEO(国巨)")
        (field (name "MANUFACTURER PART") "RT0805BRD0725RL")
        (field (name "CONTRIBUTOR") "lcsc")
      )
      (libsource (lib "altium-import") (part "root_0_25Ω_"))
    )
    (comp (ref "R154")
      (value "25Ω")
      (fields
        (field (name "MANUFACTURER") "YAGEO(国巨)")
        (field (name "MANUFACTURER PART") "RT0805BRD0725RL")
        (field (name "CONTRIBUTOR") "lcsc")
      )
      (libsource (lib "altium-import") (part "root_0_25Ω_"))
    )
    (comp (ref "R155")
      (value "25Ω")
      (fields
        (field (name "MANUFACTURER") "YAGEO(国巨)")
        (field (name "MANUFACTURER PART") "RT0805BRD0725RL")
        (field (name "CONTRIBUTOR") "lcsc")
      )
      (libsource (lib "altium-import") (part "root_0_25Ω_"))
    )
    (comp (ref "R156")
      (value "25Ω")
      (fields
        (field (name "MANUFACTURER") "YAGEO(国巨)")
        (field (name "MANUFACTURER PART") "RT0805BRD0725RL")
        (field (name "CONTRIBUTOR") "lcsc")
      )
      (libsource (lib "altium-import") (part "root_0_25Ω_"))
    )
    (comp (ref "R157")
      (value "25Ω")
      (fields
        (field (name "MANUFACTURER") "YAGEO(国巨)")
        (field (name "MANUFACTURER PART") "RT0805BRD0725RL")
        (field (name "CONTRIBUTOR") "lcsc")
      )
      (libsource (lib "altium-import") (part "root_0_25Ω_"))
    )
    (comp (ref "R158")
      (value "25Ω")
      (fields
        (field (name "MANUFACTURER") "YAGEO(国巨)")
        (field (name "MANUFACTURER PART") "RT0805BRD0725RL")
        (field (name "CONTRIBUTOR") "lcsc")
      )
      (libsource (lib "altium-import") (part "root_0_25Ω_"))
    )
    (comp (ref "R159")
      (value "25Ω")
      (fields
        (field (name "MANUFACTURER") "YAGEO(国巨)")
        (field (name "MANUFACTURER PART") "RT0805BRD0725RL")
        (field (name "CONTRIBUTOR") "lcsc")
      )
      (libsource (lib "altium-import") (part "root_0_25Ω_"))
    )
    (comp (ref "R160")
      (value "25Ω")
      (fields
        (field (name "MANUFACTURER") "YAGEO(国巨)")
        (field (name "MANUFACTURER PART") "RT0805BRD0725RL")
        (field (name "CONTRIBUTOR") "lcsc")
      )
      (libsource (lib "altium-import") (part "root_0_25Ω_"))
    )
    (comp (ref "U1")
      (value "PICO W")
      (fields (field (name "MANUFACTURER") "Raspberry Pi(树莓派)") (field (name "CONTRIBUTOR") "lcsc"))
      (libsource (lib "altium-import") (part "root_0_PICO W_"))
    )
    (comp (ref "U2")
      (value "BX-PZ2.54-2-10PZZ")
      (fields (field (name "MANUFACTURER") "Bossie(博锡)") (field (name "CONTRIBUTOR") "lcsc"))
      (libsource (lib "altium-import") (part "root_0_BX-PZ2.54-2-10PZZ_"))
    )
    (comp (ref "U3")
      (value "BX-PZ2.54-2-10PZZ")
      (fields (field (name "MANUFACTURER") "Bossie(博锡)") (field (name "CONTRIBUTOR") "lcsc"))
      (libsource (lib "altium-import") (part "root_0_BX-PZ2.54-2-10PZZ_"))
    )
    (comp (ref "U4")
      (value "BX-PZ2.54-2-10PZZ")
      (fields (field (name "MANUFACTURER") "Bossie(博锡)") (field (name "CONTRIBUTOR") "lcsc"))
      (libsource (lib "altium-import") (part "root_0_BX-PZ2.54-2-10PZZ_"))
    )
    (comp (ref "U5")
      (value "BX-PZ2.54-2-10PZZ")
      (fields (field (name "MANUFACTURER") "Bossie(博锡)") (field (name "CONTRIBUTOR") "lcsc"))
      (libsource (lib "altium-import") (part "root_0_BX-PZ2.54-2-10PZZ_"))
    )
    (comp (ref "U6")
      (value "BX-PZ2.54-2-10PZZ")
      (fields (field (name "MANUFACTURER") "Bossie(博锡)") (field (name "CONTRIBUTOR") "lcsc"))
      (libsource (lib "altium-import") (part "root_0_BX-PZ2.54-2-10PZZ_"))
    )
    (comp (ref "U7")
      (value "BX-PZ2.54-2-10PZZ")
      (fields (field (name "MANUFACTURER") "Bossie(博锡)") (field (name "CONTRIBUTOR") "lcsc"))
      (libsource (lib "altium-import") (part "root_0_BX-PZ2.54-2-10PZZ_"))
    )
    (comp (ref "U8")
      (value "TPL7407LADR")
      (fields (field (name "MANUFACTURER") "TI(德州仪器)") (field (name "CONTRIBUTOR") "LCSC"))
      (libsource (lib "altium-import") (part "root_1_TPL7407LADR_"))
    )
    (comp (ref "U9")
      (value "TPL7407LADR")
      (fields (field (name "MANUFACTURER") "TI(德州仪器)") (field (name "CONTRIBUTOR") "LCSC"))
      (libsource (lib "altium-import") (part "root_0_TPL7407LADR_"))
    )
    (comp (ref "U10")
      (value "BX-PZ2.54-2-10PZZ")
      (fields (field (name "MANUFACTURER") "Bossie(博锡)") (field (name "CONTRIBUTOR") "lcsc"))
      (libsource (lib "altium-import") (part "root_0_BX-PZ2.54-2-10PZZ_"))
    )
    (comp (ref "U11")
      (value "BX-PZ2.54-2-10PZZ")
      (fields (field (name "MANUFACTURER") "Bossie(博锡)") (field (name "CONTRIBUTOR") "lcsc"))
      (libsource (lib "altium-import") (part "root_0_BX-PZ2.54-2-10PZZ_"))
    )
    (comp (ref "U12")
      (value "BX-PZ2.54-2-10PZZ")
      (fields (field (name "MANUFACTURER") "Bossie(博锡)") (field (name "CONTRIBUTOR") "lcsc"))
      (libsource (lib "altium-import") (part "root_0_BX-PZ2.54-2-10PZZ_"))
    )
    (comp (ref "U13")
      (value "BX-PZ2.54-2-10PZZ")
      (fields (field (name "MANUFACTURER") "Bossie(博锡)") (field (name "CONTRIBUTOR") "lcsc"))
      (libsource (lib "altium-import") (part "root_0_BX-PZ2.54-2-10PZZ_"))
    )
    (comp (ref "U14")
      (value "BX-PZ2.54-2-10PZZ")
      (fields (field (name "MANUFACTURER") "Bossie(博锡)") (field (name "CONTRIBUTOR") "lcsc"))
      (libsource (lib "altium-import") (part "root_0_BX-PZ2.54-2-10PZZ_"))
    )
    (comp (ref "U15")
      (value "BX-PZ2.54-2-10PZZ")
      (fields (field (name "MANUFACTURER") "Bossie(博锡)") (field (name "CONTRIBUTOR") "lcsc"))
      (libsource (lib "altium-import") (part "root_0_BX-PZ2.54-2-10PZZ_"))
    )
    (comp (ref "U16")
      (value "BX-PZ2.54-2-10PZZ")
      (fields (field (name "MANUFACTURER") "Bossie(博锡)") (field (name "CONTRIBUTOR") "lcsc"))
      (libsource (lib "altium-import") (part "root_0_BX-PZ2.54-2-10PZZ_"))
    )
    (comp (ref "U17")
      (value "BX-PZ2.54-2-10PZZ")
      (fields (field (name "MANUFACTURER") "Bossie(博锡)") (field (name "CONTRIBUTOR") "lcsc"))
      (libsource (lib "altium-import") (part "root_0_BX-PZ2.54-2-10PZZ_"))
    )
    (comp (ref "U18")
      (value "TPL7407LADR")
      (fields (field (name "MANUFACTURER") "TI(德州仪器)") (field (name "CONTRIBUTOR") "LCSC"))
      (libsource (lib "altium-import") (part "root_0_TPL7407LADR_"))
    )
    (comp (ref "U19")
      (value "BX-PZ2.54-2-10PZZ")
      (fields (field (name "MANUFACTURER") "Bossie(博锡)") (field (name "CONTRIBUTOR") "lcsc"))
      (libsource (lib "altium-import") (part "root_0_BX-PZ2.54-2-10PZZ_"))
    )
    (comp (ref "U20")
      (value "BX-PZ2.54-2-10PZZ")
      (fields (field (name "MANUFACTURER") "Bossie(博锡)") (field (name "CONTRIBUTOR") "lcsc"))
      (libsource (lib "altium-import") (part "root_0_BX-PZ2.54-2-10PZZ_"))
    )
    (comp (ref "U21")
      (value "5-146252-6")
      (fields (field (name "MANUFACTURER") "TE Connectivity(泰科电子)") (field (name "CONTRIBUTOR") "lcsc"))
      (libsource (lib "altium-import") (part "root_0_5-146252-6_"))
    )
    (comp (ref "U22")
      (value "PM254-2-08-Z-8.5")
      (fields (field (name "MANUFACTURER") "HCTL(华灿天禄)") (field (name "CONTRIBUTOR") "LCSC"))
      (libsource (lib "altium-import") (part "root_3_PM254-2-08-Z-8.5_"))
    )
    (comp (ref "U23")
      (value "TPL7407LADR")
      (fields (field (name "MANUFACTURER") "TI(德州仪器)") (field (name "CONTRIBUTOR") "LCSC"))
      (libsource (lib "altium-import") (part "root_0_TPL7407LADR_"))
    )
    (comp (ref "U24")
      (value "100nF")
      (fields
        (field (name "MANUFACTURER") "YAGEO(国巨)")
        (field (name "MANUFACTURER PART") "CC0805KKX7RYBB104")
        (field (name "CONTRIBUTOR") "lcsc")
      )
      (libsource (lib "altium-import") (part "root_1_100nF_"))
    )
    (comp (ref "U25")
      (value "100nF")
      (fields
        (field (name "MANUFACTURER") "YAGEO(国巨)")
        (field (name "MANUFACTURER PART") "CC0805KKX7RYBB104")
        (field (name "CONTRIBUTOR") "lcsc")
      )
      (libsource (lib "altium-import") (part "root_2_100nF_"))
    )
    (comp (ref "U26")
      (value "100nF")
      (fields
        (field (name "MANUFACTURER") "YAGEO(国巨)")
        (field (name "MANUFACTURER PART") "CC0805KKX7RYBB104")
        (field (name "CONTRIBUTOR") "lcsc")
      )
      (libsource (lib "altium-import") (part "root_2_100nF_"))
    )
    (comp (ref "U27")
      (value "100nF")
      (fields
        (field (name "MANUFACTURER") "YAGEO(国巨)")
        (field (name "MANUFACTURER PART") "CC0805KKX7RYBB104")
        (field (name "CONTRIBUTOR") "lcsc")
      )
      (libsource (lib "altium-import") (part "root_2_100nF_"))
    )
    (comp (ref "U28")
      (value "100nF")
      (fields
        (field (name "MANUFACTURER") "YAGEO(国巨)")
        (field (name "MANUFACTURER PART") "CC0805KKX7RYBB104")
        (field (name "CONTRIBUTOR") "lcsc")
      )
      (libsource (lib "altium-import") (part "root_3_100nF_"))
    )
    (comp (ref "U37")
      (value "PM254-2-08-Z-8.5")
      (fields (field (name "MANUFACTURER") "HCTL(华灿天禄)") (field (name "CONTRIBUTOR") "LCSC"))
      (libsource (lib "altium-import") (part "root_2_PM254-2-08-Z-8.5_"))
    )
  )
  (nets
    (net (code "1") (name "GND") (class "Default")
      (node (ref "C3") (pin "2") (pinfunction "2_2") (pintype "passive"))
      (node (ref "U1") (pin "38") (pinfunction "GND_38") (pintype "passive"))
      (node (ref "U18") (pin "8") (pinfunction "GND_8") (pintype "passive"))
      (node (ref "U21") (pin "3") (pinfunction "3_3") (pintype "passive"))
      (node (ref "U21") (pin "4") (pinfunction "4_4") (pintype "passive"))
      (node (ref "U23") (pin "8") (pinfunction "GND_8") (pintype "passive"))
      (node (ref "U24") (pin "1") (pinfunction "1_1") (pintype "passive"))
      (node (ref "U25") (pin "2") (pinfunction "2_2") (pintype "passive"))
      (node (ref "U26") (pin "2") (pinfunction "2_2") (pintype "passive"))
      (node (ref "U27") (pin "2") (pinfunction "2_2") (pintype "passive"))
      (node (ref "U28") (pin "2") (pinfunction "2_2") (pintype "passive"))
      (node (ref "U8") (pin "8") (pinfunction "GND_8") (pintype "passive"))
      (node (ref "U9") (pin "8") (pinfunction "GND_8") (pintype "passive"))
    )
    (net (code "2") (name "Net-(R1-Pad2)") (class "Default")
      (node (ref "R1") (pin "2") (pinfunction "2_2") (pintype "passive"))
      (node (ref "U10") (pin "19") (pinfunction "19_19") (pintype "passive"))
    )
    (net (code "3") (name "Net-(R2-Pad2)") (class "Default")
      (node (ref "R2") (pin "2") (pinfunction "2_2") (pintype "passive"))
      (node (ref "U2") (pin "1") (pinfunction "1_1") (pintype "passive"))
    )
    (net (code "4") (name "Net-(R3-Pad2)") (class "Default")
      (node (ref "R3") (pin "2") (pinfunction "2_2") (pintype "passive"))
      (node (ref "U2") (pin "3") (pinfunction "3_3") (pintype "passive"))
    )
    (net (code "5") (name "Net-(R4-Pad2)") (class "Default")
      (node (ref "R4") (pin "2") (pinfunction "2_2") (pintype "passive"))
      (node (ref "U2") (pin "5") (pinfunction "5_5") (pintype "passive"))
    )
    (net (code "6") (name "Net-(R5-Pad2)") (class "Default")
      (node (ref "R5") (pin "2") (pinfunction "2_2") (pintype "passive"))
      (node (ref "U2") (pin "7") (pinfunction "7_7") (pintype "passive"))
    )
    (net (code "7") (name "Net-(R6-Pad2)") (class "Default")
      (node (ref "R6") (pin "2") (pinfunction "2_2") (pintype "passive"))
      (node (ref "U2") (pin "9") (pinfunction "9_9") (pintype "passive"))
    )
    (net (code "8") (name "Net-(R7-Pad2)") (class "Default")
      (node (ref "R7") (pin "2") (pinfunction "2_2") (pintype "passive"))
      (node (ref "U2") (pin "11") (pinfunction "11_11") (pintype "passive"))
    )
    (net (code "9") (name "Net-(R8-Pad2)") (class "Default")
      (node (ref "R8") (pin "2") (pinfunction "2_2") (pintype "passive"))
      (node (ref "U2") (pin "13") (pinfunction "13_13") (pintype "passive"))
    )
    (net (code "10") (name "Net-(R9-Pad2)") (class "Default")
      (node (ref "R9") (pin "2") (pinfunction "2_2") (pintype "passive"))
      (node (ref "U2") (pin "15") (pinfunction "15_15") (pintype "passive"))
    )
    (net (code "11") (name "Net-(R10-Pad2)") (class "Default")
      (node (ref "R10") (pin "2") (pinfunction "2_2") (pintype "passive"))
      (node (ref "U2") (pin "17") (pinfunction "17_17") (pintype "passive"))
    )
    (net (code "12") (name "Net-(R11-Pad2)") (class "Default")
      (node (ref "R11") (pin "2") (pinfunction "2_2") (pintype "passive"))
      (node (ref "U2") (pin "19") (pinfunction "19_19") (pintype "passive"))
    )
    (net (code "13") (name "Net-(R12-Pad2)") (class "Default")
      (node (ref "R12") (pin "2") (pinfunction "2_2") (pintype "passive"))
      (node (ref "U3") (pin "19") (pinfunction "19_19") (pintype "passive"))
    )
    (net (code "14") (name "Net-(R13-Pad2)") (class "Default")
      (node (ref "R13") (pin "2") (pinfunction "2_2") (pintype "passive"))
      (node (ref "U3") (pin "17") (pinfunction "17_17") (pintype "passive"))
    )
    (net (code "15") (name "Net-(R14-Pad2)") (class "Default")
      (node (ref "R14") (pin "2") (pinfunction "2_2") (pintype "passive"))
      (node (ref "U3") (pin "15") (pinfunction "15_15") (pintype "passive"))
    )
    (net (code "16") (name "Net-(R15-Pad2)") (class "Default")
      (node (ref "R15") (pin "2") (pinfunction "2_2") (pintype "passive"))
      (node (ref "U3") (pin "13") (pinfunction "13_13") (pintype "passive"))
    )
    (net (code "17") (name "Net-(R16-Pad2)") (class "Default")
      (node (ref "R16") (pin "2") (pinfunction "2_2") (pintype "passive"))
      (node (ref "U3") (pin "11") (pinfunction "11_11") (pintype "passive"))
    )
    (net (code "18") (name "Net-(R17-Pad2)") (class "Default")
      (node (ref "R17") (pin "2") (pinfunction "2_2") (pintype "passive"))
      (node (ref "U3") (pin "9") (pinfunction "9_9") (pintype "passive"))
    )
    (net (code "19") (name "Net-(R18-Pad2)") (class "Default")
      (node (ref "R18") (pin "2") (pinfunction "2_2") (pintype "passive"))
      (node (ref "U3") (pin "7") (pinfunction "7_7") (pintype "passive"))
    )
    (net (code "20") (name "Net-(R19-Pad2)") (class "Default")
      (node (ref "R19") (pin "2") (pinfunction "2_2") (pintype "passive"))
      (node (ref "U3") (pin "5") (pinfunction "5_5") (pintype "passive"))
    )
    (net (code "21") (name "Net-(R20-Pad2)") (class "Default")
      (node (ref "R20") (pin "2") (pinfunction "2_2") (pintype "passive"))
      (node (ref "U3") (pin "3") (pinfunction "3_3") (pintype "passive"))
    )
    (net (code "22") (name "Net-(R21-Pad2)") (class "Default")
      (node (ref "R21") (pin "2") (pinfunction "2_2") (pintype "passive"))
      (node (ref "U3") (pin "1") (pinfunction "1_1") (pintype "passive"))
    )
    (net (code "23") (name "Net-(R22-Pad2)") (class "Default")
      (node (ref "R22") (pin "2") (pinfunction "2_2") (pintype "passive"))
      (node (ref "U4") (pin "1") (pinfunction "1_1") (pintype "passive"))
    )
    (net (code "24") (name "Net-(R23-Pad2)") (class "Default")
      (node (ref "R23") (pin "2") (pinfunction "2_2") (pintype "passive"))
      (node (ref "U4") (pin "3") (pinfunction "3_3") (pintype "passive"))
    )
    (net (code "25") (name "Net-(R24-Pad2)") (class "Default")
      (node (ref "R24") (pin "2") (pinfunction "2_2") (pintype "passive"))
      (node (ref "U4") (pin "5") (pinfunction "5_5") (pintype "passive"))
    )
    (net (code "26") (name "Net-(R25-Pad2)") (class "Default")
      (node (ref "R25") (pin "2") (pinfunction "2_2") (pintype "passive"))
      (node (ref "U4") (pin "7") (pinfunction "7_7") (pintype "passive"))
    )
    (net (code "27") (name "Net-(R26-Pad2)") (class "Default")
      (node (ref "R26") (pin "2") (pinfunction "2_2") (pintype "passive"))
      (node (ref "U4") (pin "9") (pinfunction "9_9") (pintype "passive"))
    )
    (net (code "28") (name "Net-(R27-Pad2)") (class "Default")
      (node (ref "R27") (pin "2") (pinfunction "2_2") (pintype "passive"))
      (node (ref "U4") (pin "11") (pinfunction "11_11") (pintype "passive"))
    )
    (net (code "29") (name "Net-(R28-Pad2)") (class "Default")
      (node (ref "R28") (pin "2") (pinfunction "2_2") (pintype "passive"))
      (node (ref "U4") (pin "13") (pinfunction "13_13") (pintype "passive"))
    )
    (net (code "30") (name "Net-(R29-Pad2)") (class "Default")
      (node (ref "R29") (pin "2") (pinfunction "2_2") (pintype "passive"))
      (node (ref "U4") (pin "15") (pinfunction "15_15") (pintype "passive"))
    )
    (net (code "31") (name "Net-(R30-Pad2)") (class "Default")
      (node (ref "R30") (pin "2") (pinfunction "2_2") (pintype "passive"))
      (node (ref "U4") (pin "17") (pinfunction "17_17") (pintype "passive"))
    )
    (net (code "32") (name "Net-(R31-Pad2)") (class "Default")
      (node (ref "R31") (pin "2") (pinfunction "2_2") (pintype "passive"))
      (node (ref "U4") (pin "19") (pinfunction "19_19") (pintype "passive"))
    )
    (net (code "33") (name "Net-(R32-Pad2)") (class "Default")
      (node (ref "R32") (pin "2") (pinfunction "2_2") (pintype "passive"))
      (node (ref "U10") (pin "17") (pinfunction "17_17") (pintype "passive"))
    )
    (net (code "34") (name "Net-(R33-Pad2)") (class "Default")
      (node (ref "R33") (pin "2") (pinfunction "2_2") (pintype "passive"))
      (node (ref "U5") (pin "19") (pinfunction "19_19") (pintype "passive"))
    )
    (net (code "35") (name "Net-(R34-Pad2)") (class "Default")
      (node (ref "R34") (pin "2") (pinfunction "2_2") (pintype "passive"))
      (node (ref "U5") (pin "17") (pinfunction "17_17") (pintype "passive"))
    )
    (net (code "36") (name "Net-(R35-Pad2)") (class "Default")
      (node (ref "R35") (pin "2") (pinfunction "2_2") (pintype "passive"))
      (node (ref "U5") (pin "15") (pinfunction "15_15") (pintype "passive"))
    )
    (net (code "37") (name "Net-(R36-Pad2)") (class "Default")
      (node (ref "R36") (pin "2") (pinfunction "2_2") (pintype "passive"))
      (node (ref "U5") (pin "13") (pinfunction "13_13") (pintype "passive"))
    )
    (net (code "38") (name "Net-(R37-Pad2)") (class "Default")
      (node (ref "R37") (pin "2") (pinfunction "2_2") (pintype "passive"))
      (node (ref "U5") (pin "11") (pinfunction "11_11") (pintype "passive"))
    )
    (net (code "39") (name "Net-(R38-Pad2)") (class "Default")
      (node (ref "R38") (pin "2") (pinfunction "2_2") (pintype "passive"))
      (node (ref "U5") (pin "9") (pinfunction "9_9") (pintype "passive"))
    )
    (net (code "40") (name "Net-(R39-Pad2)") (class "Default")
      (node (ref "R39") (pin "2") (pinfunction "2_2") (pintype "passive"))
      (node (ref "U5") (pin "7") (pinfunction "7_7") (pintype "passive"))
    )
    (net (code "41") (name "Net-(R40-Pad2)") (class "Default")
      (node (ref "R40") (pin "2") (pinfunction "2_2") (pintype "passive"))
      (node (ref "U5") (pin "5") (pinfunction "5_5") (pintype "passive"))
    )
    (net (code "42") (name "Net-(R41-Pad2)") (class "Default")
      (node (ref "R41") (pin "2") (pinfunction "2_2") (pintype "passive"))
      (node (ref "U5") (pin "3") (pinfunction "3_3") (pintype "passive"))
    )
    (net (code "43") (name "Net-(R42-Pad2)") (class "Default")
      (node (ref "R42") (pin "2") (pinfunction "2_2") (pintype "passive"))
      (node (ref "U5") (pin "1") (pinfunction "1_1") (pintype "passive"))
    )
    (net (code "44") (name "Net-(R43-Pad2)") (class "Default")
      (node (ref "R43") (pin "2") (pinfunction "2_2") (pintype "passive"))
      (node (ref "U6") (pin "1") (pinfunction "1_1") (pintype "passive"))
    )
    (net (code "45") (name "Net-(R44-Pad2)") (class "Default")
      (node (ref "R44") (pin "2") (pinfunction "2_2") (pintype "passive"))
      (node (ref "U6") (pin "3") (pinfunction "3_3") (pintype "passive"))
    )
    (net (code "46") (name "Net-(R45-Pad2)") (class "Default")
      (node (ref "R45") (pin "2") (pinfunction "2_2") (pintype "passive"))
      (node (ref "U6") (pin "5") (pinfunction "5_5") (pintype "passive"))
    )
    (net (code "47") (name "Net-(R46-Pad2)") (class "Default")
      (node (ref "R46") (pin "2") (pinfunction "2_2") (pintype "passive"))
      (node (ref "U6") (pin "7") (pinfunction "7_7") (pintype "passive"))
    )
    (net (code "48") (name "Net-(R47-Pad2)") (class "Default")
      (node (ref "R47") (pin "2") (pinfunction "2_2") (pintype "passive"))
      (node (ref "U6") (pin "9") (pinfunction "9_9") (pintype "passive"))
    )
    (net (code "49") (name "Net-(R48-Pad2)") (class "Default")
      (node (ref "R48") (pin "2") (pinfunction "2_2") (pintype "passive"))
      (node (ref "U6") (pin "11") (pinfunction "11_11") (pintype "passive"))
    )
    (net (code "50") (name "Net-(R49-Pad2)") (class "Default")
      (node (ref "R49") (pin "2") (pinfunction "2_2") (pintype "passive"))
      (node (ref "U6") (pin "13") (pinfunction "13_13") (pintype "passive"))
    )
    (net (code "51") (name "Net-(R50-Pad2)") (class "Default")
      (node (ref "R50") (pin "2") (pinfunction "2_2") (pintype "passive"))
      (node (ref "U6") (pin "15") (pinfunction "15_15") (pintype "passive"))
    )
    (net (code "52") (name "Net-(R51-Pad2)") (class "Default")
      (node (ref "R51") (pin "2") (pinfunction "2_2") (pintype "passive"))
      (node (ref "U6") (pin "17") (pinfunction "17_17") (pintype "passive"))
    )
    (net (code "53") (name "Net-(R52-Pad2)") (class "Default")
      (node (ref "R52") (pin "2") (pinfunction "2_2") (pintype "passive"))
      (node (ref "U6") (pin "19") (pinfunction "19_19") (pintype "passive"))
    )
    (net (code "54") (name "Net-(R53-Pad2)") (class "Default")
      (node (ref "R53") (pin "2") (pinfunction "2_2") (pintype "passive"))
      (node (ref "U7") (pin "1") (pinfunction "1_1") (pintype "passive"))
    )
    (net (code "55") (name "Net-(R54-Pad2)") (class "Default")
      (node (ref "R54") (pin "2") (pinfunction "2_2") (pintype "passive"))
      (node (ref "U7") (pin "3") (pinfunction "3_3") (pintype "passive"))
    )
    (net (code "56") (name "Net-(R55-Pad2)") (class "Default")
      (node (ref "R55") (pin "2") (pinfunction "2_2") (pintype "passive"))
      (node (ref "U7") (pin "5") (pinfunction "5_5") (pintype "passive"))
    )
    (net (code "57") (name "Net-(R56-Pad2)") (class "Default")
      (node (ref "R56") (pin "2") (pinfunction "2_2") (pintype "passive"))
      (node (ref "U7") (pin "7") (pinfunction "7_7") (pintype "passive"))
    )
    (net (code "58") (name "Net-(R57-Pad2)") (class "Default")
      (node (ref "R57") (pin "2") (pinfunction "2_2") (pintype "passive"))
      (node (ref "U7") (pin "9") (pinfunction "9_9") (pintype "passive"))
    )
    (net (code "59") (name "Net-(R58-Pad2)") (class "Default")
      (node (ref "R58") (pin "2") (pinfunction "2_2") (pintype "passive"))
      (node (ref "U7") (pin "11") (pinfunction "11_11") (pintype "passive"))
    )
    (net (code "60") (name "Net-(R59-Pad2)") (class "Default")
      (node (ref "R59") (pin "2") (pinfunction "2_2") (pintype "passive"))
      (node (ref "U7") (pin "13") (pinfunction "13_13") (pintype "passive"))
    )
    (net (code "61") (name "Net-(R60-Pad2)") (class "Default")
      (node (ref "R60") (pin "2") (pinfunction "2_2") (pintype "passive"))
      (node (ref "U7") (pin "15") (pinfunction "15_15") (pintype "passive"))
    )
    (net (code "62") (name "Net-(R61-Pad2)") (class "Default")
      (node (ref "R61") (pin "2") (pinfunction "2_2") (pintype "passive"))
      (node (ref "U7") (pin "17") (pinfunction "17_17") (pintype "passive"))
    )
    (net (code "63") (name "Net-(R62-Pad2)") (class "Default")
      (node (ref "R62") (pin "2") (pinfunction "2_2") (pintype "passive"))
      (node (ref "U7") (pin "19") (pinfunction "19_19") (pintype "passive"))
    )
    (net (code "64") (name "Net-(R63-Pad2)") (class "Default")
      (node (ref "R63") (pin "2") (pinfunction "2_2") (pintype "passive"))
      (node (ref "U10") (pin "15") (pinfunction "15_15") (pintype "passive"))
    )
    (net (code "65") (name "Net-(R64-Pad2)") (class "Default")
      (node (ref "R64") (pin "2") (pinfunction "2_2") (pintype "passive"))
      (node (ref "U10") (pin "13") (pinfunction "13_13") (pintype "passive"))
    )
    (net (code "66") (name "Net-(R65-Pad2)") (class "Default")
      (node (ref "R65") (pin "2") (pinfunction "2_2") (pintype "passive"))
      (node (ref "U10") (pin "11") (pinfunction "11_11") (pintype "passive"))
    )
    (net (code "67") (name "Net-(R66-Pad2)") (class "Default")
      (node (ref "R66") (pin "2") (pinfunction "2_2") (pintype "passive"))
      (node (ref "U10") (pin "9") (pinfunction "9_9") (pintype "passive"))
    )
    (net (code "68") (name "Net-(R67-Pad2)") (class "Default")
      (node (ref "R67") (pin "2") (pinfunction "2_2") (pintype "passive"))
      (node (ref "U10") (pin "7") (pinfunction "7_7") (pintype "passive"))
    )
    (net (code "69") (name "Net-(R68-Pad2)") (class "Default")
      (node (ref "R68") (pin "2") (pinfunction "2_2") (pintype "passive"))
      (node (ref "U10") (pin "5") (pinfunction "5_5") (pintype "passive"))
    )
    (net (code "70") (name "Net-(R69-Pad2)") (class "Default")
      (node (ref "R69") (pin "2") (pinfunction "2_2") (pintype "passive"))
      (node (ref "U10") (pin "3") (pinfunction "3_3") (pintype "passive"))
    )
    (net (code "71") (name "Net-(R70-Pad2)") (class "Default")
      (node (ref "R70") (pin "2") (pinfunction "2_2") (pintype "passive"))
      (node (ref "U10") (pin "1") (pinfunction "1_1") (pintype "passive"))
    )
    (net (code "72") (name "Net-(R71-Pad2)") (class "Default")
      (node (ref "R71") (pin "2") (pinfunction "2_2") (pintype "passive"))
      (node (ref "U11") (pin "19") (pinfunction "19_19") (pintype "passive"))
    )
    (net (code "73") (name "Net-(R72-Pad2)") (class "Default")
      (node (ref "R72") (pin "2") (pinfunction "2_2") (pintype "passive"))
      (node (ref "U11") (pin "17") (pinfunction "17_17") (pintype "passive"))
    )
    (net (code "74") (name "Net-(R73-Pad2)") (class "Default")
      (node (ref "R73") (pin "2") (pinfunction "2_2") (pintype "passive"))
      (node (ref "U11") (pin "15") (pinfunction "15_15") (pintype "passive"))
    )
    (net (code "75") (name "Net-(R74-Pad2)") (class "Default")
      (node (ref "R74") (pin "2") (pinfunction "2_2") (pintype "passive"))
      (node (ref "U11") (pin "13") (pinfunction "13_13") (pintype "passive"))
    )
    (net (code "76") (name "Net-(R75-Pad2)") (class "Default")
      (node (ref "R75") (pin "2") (pinfunction "2_2") (pintype "passive"))
      (node (ref "U11") (pin "11") (pinfunction "11_11") (pintype "passive"))
    )
    (net (code "77") (name "Net-(R76-Pad2)") (class "Default")
      (node (ref "R76") (pin "2") (pinfunction "2_2") (pintype "passive"))
      (node (ref "U11") (pin "9") (pinfunction "9_9") (pintype "passive"))
    )
    (net (code "78") (name "Net-(R77-Pad2)") (class "Default")
      (node (ref "R77") (pin "2") (pinfunction "2_2") (pintype "passive"))
      (node (ref "U11") (pin "7") (pinfunction "7_7") (pintype "passive"))
    )
    (net (code "79") (name "Net-(R78-Pad2)") (class "Default")
      (node (ref "R78") (pin "2") (pinfunction "2_2") (pintype "passive"))
      (node (ref "U11") (pin "5") (pinfunction "5_5") (pintype "passive"))
    )
    (net (code "80") (name "Net-(R79-Pad2)") (class "Default")
      (node (ref "R79") (pin "2") (pinfunction "2_2") (pintype "passive"))
      (node (ref "U11") (pin "3") (pinfunction "3_3") (pintype "passive"))
    )
    (net (code "81") (name "Net-(R80-Pad2)") (class "Default")
      (node (ref "R80") (pin "2") (pinfunction "2_2") (pintype "passive"))
      (node (ref "U11") (pin "1") (pinfunction "1_1") (pintype "passive"))
    )
    (net (code "82") (name "Net-(R81-Pad2)") (class "Default")
      (node (ref "R81") (pin "2") (pinfunction "2_2") (pintype "passive"))
      (node (ref "U12") (pin "19") (pinfunction "19_19") (pintype "passive"))
    )
    (net (code "83") (name "Net-(R82-Pad2)") (class "Default")
      (node (ref "R82") (pin "2") (pinfunction "2_2") (pintype "passive"))
      (node (ref "U12") (pin "17") (pinfunction "17_17") (pintype "passive"))
    )
    (net (code "84") (name "Net-(R83-Pad2)") (class "Default")
      (node (ref "R83") (pin "2") (pinfunction "2_2") (pintype "passive"))
      (node (ref "U12") (pin "15") (pinfunction "15_15") (pintype "passive"))
    )
    (net (code "85") (name "Net-(R84-Pad2)") (class "Default")
      (node (ref "R84") (pin "2") (pinfunction "2_2") (pintype "passive"))
      (node (ref "U12") (pin "13") (pinfunction "13_13") (pintype "passive"))
    )
    (net (code "86") (name "Net-(R85-Pad2)") (class "Default")
      (node (ref "R85") (pin "2") (pinfunction "2_2") (pintype "passive"))
      (node (ref "U12") (pin "11") (pinfunction "11_11") (pintype "passive"))
    )
    (net (code "87") (name "Net-(R86-Pad2)") (class "Default")
      (node (ref "R86") (pin "2") (pinfunction "2_2") (pintype "passive"))
      (node (ref "U12") (pin "9") (pinfunction "9_9") (pintype "passive"))
    )
    (net (code "88") (name "Net-(R87-Pad2)") (class "Default")
      (node (ref "R87") (pin "2") (pinfunction "2_2") (pintype "passive"))
      (node (ref "U12") (pin "7") (pinfunction "7_7") (pintype "passive"))
    )
    (net (code "89") (name "Net-(R88-Pad2)") (class "Default")
      (node (ref "R88") (pin "2") (pinfunction "2_2") (pintype "passive"))
      (node (ref "U12") (pin "5") (pinfunction "5_5") (pintype "passive"))
    )
    (net (code "90") (name "Net-(R89-Pad2)") (class "Default")
      (node (ref "R89") (pin "2") (pinfunction "2_2") (pintype "passive"))
      (node (ref "U12") (pin "3") (pinfunction "3_3") (pintype "passive"))
    )
    (net (code "91") (name "Net-(R90-Pad2)") (class "Default")
      (node (ref "R90") (pin "2") (pinfunction "2_2") (pintype "passive"))
      (node (ref "U12") (pin "1") (pinfunction "1_1") (pintype "passive"))
    )
    (net (code "92") (name "Net-(R91-Pad2)") (class "Default")
      (node (ref "R91") (pin "2") (pinfunction "2_2") (pintype "passive"))
      (node (ref "U13") (pin "19") (pinfunction "19_19") (pintype "passive"))
    )
    (net (code "93") (name "Net-(R92-Pad2)") (class "Default")
      (node (ref "R92") (pin "2") (pinfunction "2_2") (pintype "passive"))
      (node (ref "U13") (pin "17") (pinfunction "17_17") (pintype "passive"))
    )
    (net (code "94") (name "Net-(R93-Pad2)") (class "Default")
      (node (ref "R93") (pin "2") (pinfunction "2_2") (pintype "passive"))
      (node (ref "U13") (pin "15") (pinfunction "15_15") (pintype "passive"))
    )
    (net (code "95") (name "Net-(R94-Pad2)") (class "Default")
      (node (ref "R94") (pin "2") (pinfunction "2_2") (pintype "passive"))
      (node (ref "U13") (pin "13") (pinfunction "13_13") (pintype "passive"))
    )
    (net (code "96") (name "Net-(R95-Pad2)") (class "Default")
      (node (ref "R95") (pin "2") (pinfunction "2_2") (pintype "passive"))
      (node (ref "U13") (pin "11") (pinfunction "11_11") (pintype "passive"))
    )
    (net (code "97") (name "Net-(R96-Pad2)") (class "Default")
      (node (ref "R96") (pin "2") (pinfunction "2_2") (pintype "passive"))
      (node (ref "U13") (pin "9") (pinfunction "9_9") (pintype "passive"))
    )
    (net (code "98") (name "Net-(R97-Pad2)") (class "Default")
      (node (ref "R97") (pin "2") (pinfunction "2_2") (pintype "passive"))
      (node (ref "U13") (pin "7") (pinfunction "7_7") (pintype "passive"))
    )
    (net (code "99") (name "Net-(R98-Pad2)") (class "Default")
      (node (ref "R98") (pin "2") (pinfunction "2_2") (pintype "passive"))
      (node (ref "U13") (pin "5") (pinfunction "5_5") (pintype "passive"))
    )
    (net (code "100") (name "Net-(R99-Pad2)") (class "Default")
      (node (ref "R99") (pin "2") (pinfunction "2_2") (pintype "passive"))
      (node (ref "U13") (pin "3") (pinfunction "3_3") (pintype "passive"))
    )
    (net (code "101") (name "Net-(R100-Pad2)") (class "Default")
      (node (ref "R100") (pin "2") (pinfunction "2_2") (pintype "passive"))
      (node (ref "U13") (pin "1") (pinfunction "1_1") (pintype "passive"))
    )
    (net (code "102") (name "Net-(R101-Pad2)") (class "Default")
      (node (ref "R101") (pin "2") (pinfunction "2_2") (pintype "passive"))
      (node (ref "U14") (pin "19") (pinfunction "19_19") (pintype "passive"))
    )
    (net (code "103") (name "Net-(R102-Pad2)") (class "Default")
      (node (ref "R102") (pin "2") (pinfunction "2_2") (pintype "passive"))
      (node (ref "U14") (pin "17") (pinfunction "17_17") (pintype "passive"))
    )
    (net (code "104") (name "Net-(R103-Pad2)") (class "Default")
      (node (ref "R103") (pin "2") (pinfunction "2_2") (pintype "passive"))
      (node (ref "U14") (pin "15") (pinfunction "15_15") (pintype "passive"))
    )
    (net (code "105") (name "Net-(R104-Pad2)") (class "Default")
      (node (ref "R104") (pin "2") (pinfunction "2_2") (pintype "passive"))
      (node (ref "U14") (pin "13") (pinfunction "13_13") (pintype "passive"))
    )
    (net (code "106") (name "Net-(R105-Pad2)") (class "Default")
      (node (ref "R105") (pin "2") (pinfunction "2_2") (pintype "passive"))
      (node (ref "U14") (pin "11") (pinfunction "11_11") (pintype "passive"))
    )
    (net (code "107") (name "Net-(R106-Pad2)") (class "Default")
      (node (ref "R106") (pin "2") (pinfunction "2_2") (pintype "passive"))
      (node (ref "U14") (pin "9") (pinfunction "9_9") (pintype "passive"))
    )
    (net (code "108") (name "Net-(R107-Pad2)") (class "Default")
      (node (ref "R107") (pin "2") (pinfunction "2_2") (pintype "passive"))
      (node (ref "U14") (pin "7") (pinfunction "7_7") (pintype "passive"))
    )
    (net (code "109") (name "Net-(R108-Pad2)") (class "Default")
      (node (ref "R108") (pin "2") (pinfunction "2_2") (pintype "passive"))
      (node (ref "U14") (pin "5") (pinfunction "5_5") (pintype "passive"))
    )
    (net (code "110") (name "Net-(R109-Pad2)") (class "Default")
      (node (ref "R109") (pin "2") (pinfunction "2_2") (pintype "passive"))
      (node (ref "U14") (pin "3") (pinfunction "3_3") (pintype "passive"))
    )
    (net (code "111") (name "Net-(R110-Pad2)") (class "Default")
      (node (ref "R110") (pin "2") (pinfunction "2_2") (pintype "passive"))
      (node (ref "U14") (pin "1") (pinfunction "1_1") (pintype "passive"))
    )
    (net (code "112") (name "Net-(R111-Pad2)") (class "Default")
      (node (ref "R111") (pin "2") (pinfunction "2_2") (pintype "passive"))
      (node (ref "U15") (pin "19") (pinfunction "19_19") (pintype "passive"))
    )
    (net (code "113") (name "Net-(R112-Pad2)") (class "Default")
      (node (ref "R112") (pin "2") (pinfunction "2_2") (pintype "passive"))
      (node (ref "U15") (pin "17") (pinfunction "17_17") (pintype "passive"))
    )
    (net (code "114") (name "Net-(R113-Pad2)") (class "Default")
      (node (ref "R113") (pin "2") (pinfunction "2_2") (pintype "passive"))
      (node (ref "U15") (pin "15") (pinfunction "15_15") (pintype "passive"))
    )
    (net (code "115") (name "Net-(R114-Pad2)") (class "Default")
      (node (ref "R114") (pin "2") (pinfunction "2_2") (pintype "passive"))
      (node (ref "U15") (pin "13") (pinfunction "13_13") (pintype "passive"))
    )
    (net (code "116") (name "Net-(R115-Pad2)") (class "Default")
      (node (ref "R115") (pin "2") (pinfunction "2_2") (pintype "passive"))
      (node (ref "U15") (pin "11") (pinfunction "11_11") (pintype "passive"))
    )
    (net (code "117") (name "Net-(R116-Pad2)") (class "Default")
      (node (ref "R116") (pin "2") (pinfunction "2_2") (pintype "passive"))
      (node (ref "U15") (pin "9") (pinfunction "9_9") (pintype "passive"))
    )
    (net (code "118") (name "Net-(R117-Pad2)") (class "Default")
      (node (ref "R117") (pin "2") (pinfunction "2_2") (pintype "passive"))
      (node (ref "U15") (pin "7") (pinfunction "7_7") (pintype "passive"))
    )
    (net (code "119") (name "Net-(R118-Pad2)") (class "Default")
      (node (ref "R118") (pin "2") (pinfunction "2_2") (pintype "passive"))
      (node (ref "U15") (pin "5") (pinfunction "5_5") (pintype "passive"))
    )
    (net (code "120") (name "Net-(R119-Pad2)") (class "Default")
      (node (ref "R119") (pin "2") (pinfunction "2_2") (pintype "passive"))
      (node (ref "U15") (pin "3") (pinfunction "3_3") (pintype "passive"))
    )
    (net (code "121") (name "Net-(R120-Pad2)") (class "Default")
      (node (ref "R120") (pin "2") (pinfunction "2_2") (pintype "passive"))
      (node (ref "U15") (pin "1") (pinfunction "1_1") (pintype "passive"))
    )
    (net (code "122") (name "Net-(R121-Pad2)") (class "Default")
      (node (ref "R121") (pin "2") (pinfunction "2_2") (pintype "passive"))
      (node (ref "U16") (pin "19") (pinfunction "19_19") (pintype "passive"))
    )
    (net (code "123") (name "Net-(R122-Pad2)") (class "Default")
      (node (ref "R122") (pin "2") (pinfunction "2_2") (pintype "passive"))
      (node (ref "U16") (pin "17") (pinfunction "17_17") (pintype "passive"))
    )
    (net (code "124") (name "Net-(R123-Pad2)") (class "Default")
      (node (ref "R123") (pin "2") (pinfunction "2_2") (pintype "passive"))
      (node (ref "U16") (pin "15") (pinfunction "15_15") (pintype "passive"))
    )
    (net (code "125") (name "Net-(R124-Pad2)") (class "Default")
      (node (ref "R124") (pin "2") (pinfunction "2_2") (pintype "passive"))
      (node (ref "U16") (pin "13") (pinfunction "13_13") (pintype "passive"))
    )
    (net (code "126") (name "Net-(R125-Pad2)") (class "Default")
      (node (ref "R125") (pin "2") (pinfunction "2_2") (pintype "passive"))
      (node (ref "U16") (pin "11") (pinfunction "11_11") (pintype "passive"))
    )
    (net (code "127") (name "Net-(R126-Pad2)") (class "Default")
      (node (ref "R126") (pin "2") (pinfunction "2_2") (pintype "passive"))
      (node (ref "U16") (pin "9") (pinfunction "9_9") (pintype "passive"))
    )
    (net (code "128") (name "Net-(R127-Pad2)") (class "Default")
      (node (ref "R127") (pin "2") (pinfunction "2_2") (pintype "passive"))
      (node (ref "U16") (pin "7") (pinfunction "7_7") (pintype "passive"))
    )
    (net (code "129") (name "Net-(R128-Pad2)") (class "Default")
      (node (ref "R128") (pin "2") (pinfunction "2_2") (pintype "passive"))
      (node (ref "U16") (pin "5") (pinfunction "5_5") (pintype "passive"))
    )
    (net (code "130") (name "Net-(R129-Pad2)") (class "Default")
      (node (ref "R129") (pin "2") (pinfunction "2_2") (pintype "passive"))
      (node (ref "U16") (pin "3") (pinfunction "3_3") (pintype "passive"))
    )
    (net (code "131") (name "Net-(R130-Pad2)") (class "Default")
      (node (ref "R130") (pin "2") (pinfunction "2_2") (pintype "passive"))
      (node (ref "U16") (pin "1") (pinfunction "1_1") (pintype "passive"))
    )
    (net (code "132") (name "Net-(R131-Pad2)") (class "Default")
      (node (ref "R131") (pin "2") (pinfunction "2_2") (pintype "passive"))
      (node (ref "U17") (pin "19") (pinfunction "19_19") (pintype "passive"))
    )
    (net (code "133") (name "Net-(R132-Pad2)") (class "Default")
      (node (ref "R132") (pin "2") (pinfunction "2_2") (pintype "passive"))
      (node (ref "U17") (pin "17") (pinfunction "17_17") (pintype "passive"))
    )
    (net (code "134") (name "Net-(R133-Pad2)") (class "Default")
      (node (ref "R133") (pin "2") (pinfunction "2_2") (pintype "passive"))
      (node (ref "U17") (pin "15") (pinfunction "15_15") (pintype "passive"))
    )
    (net (code "135") (name "Net-(R134-Pad2)") (class "Default")
      (node (ref "R134") (pin "2") (pinfunction "2_2") (pintype "passive"))
      (node (ref "U17") (pin "13") (pinfunction "13_13") (pintype "passive"))
    )
    (net (code "136") (name "Net-(R135-Pad2)") (class "Default")
      (node (ref "R135") (pin "2") (pinfunction "2_2") (pintype "passive"))
      (node (ref "U17") (pin "11") (pinfunction "11_11") (pintype "passive"))
    )
    (net (code "137") (name "Net-(R136-Pad2)") (class "Default")
      (node (ref "R136") (pin "2") (pinfunction "2_2") (pintype "passive"))
      (node (ref "U17") (pin "9") (pinfunction "9_9") (pintype "passive"))
    )
    (net (code "138") (name "Net-(R137-Pad2)") (class "Default")
      (node (ref "R137") (pin "2") (pinfunction "2_2") (pintype "passive"))
      (node (ref "U17") (pin "7") (pinfunction "7_7") (pintype "passive"))
    )
    (net (code "139") (name "Net-(R138-Pad2)") (class "Default")
      (node (ref "R138") (pin "2") (pinfunction "2_2") (pintype "passive"))
      (node (ref "U17") (pin "5") (pinfunction "5_5") (pintype "passive"))
    )
    (net (code "140") (name "Net-(R139-Pad2)") (class "Default")
      (node (ref "R139") (pin "2") (pinfunction "2_2") (pintype "passive"))
      (node (ref "U17") (pin "3") (pinfunction "3_3") (pintype "passive"))
    )
    (net (code "141") (name "Net-(R140-Pad2)") (class "Default")
      (node (ref "R140") (pin "2") (pinfunction "2_2") (pintype "passive"))
      (node (ref "U17") (pin "1") (pinfunction "1_1") (pintype "passive"))
    )
    (net (code "142") (name "Net-(R141-Pad2)") (class "Default")
      (node (ref "R141") (pin "2") (pinfunction "2_2") (pintype "passive"))
      (node (ref "U19") (pin "1") (pinfunction "1_1") (pintype "passive"))
    )
    (net (code "143") (name "Net-(R142-Pad2)") (class "Default")
      (node (ref "R142") (pin "2") (pinfunction "2_2") (pintype "passive"))
      (node (ref "U19") (pin "3") (pinfunction "3_3") (pintype "passive"))
    )
    (net (code "144") (name "Net-(R143-Pad2)") (class "Default")
      (node (ref "R143") (pin "2") (pinfunction "2_2") (pintype "passive"))
      (node (ref "U19") (pin "5") (pinfunction "5_5") (pintype "passive"))
    )
    (net (code "145") (name "Net-(R144-Pad2)") (class "Default")
      (node (ref "R144") (pin "2") (pinfunction "2_2") (pintype "passive"))
      (node (ref "U19") (pin "7") (pinfunction "7_7") (pintype "passive"))
    )
    (net (code "146") (name "Net-(R145-Pad2)") (class "Default")
      (node (ref "R145") (pin "2") (pinfunction "2_2") (pintype "passive"))
      (node (ref "U19") (pin "9") (pinfunction "9_9") (pintype "passive"))
    )
    (net (code "147") (name "Net-(R146-Pad2)") (class "Default")
      (node (ref "R146") (pin "2") (pinfunction "2_2") (pintype "passive"))
      (node (ref "U19") (pin "11") (pinfunction "11_11") (pintype "passive"))
    )
    (net (code "148") (name "Net-(R147-Pad2)") (class "Default")
      (node (ref "R147") (pin "2") (pinfunction "2_2") (pintype "passive"))
      (node (ref "U19") (pin "13") (pinfunction "13_13") (pintype "passive"))
    )
    (net (code "149") (name "Net-(R148-Pad2)") (class "Default")
      (node (ref "R148") (pin "2") (pinfunction "2_2") (pintype "passive"))
      (node (ref "U19") (pin "15") (pinfunction "15_15") (pintype "passive"))
    )
    (net (code "150") (name "Net-(R149-Pad2)") (class "Default")
      (node (ref "R149") (pin "2") (pinfunction "2_2") (pintype "passive"))
      (node (ref "U19") (pin "17") (pinfunction "17_17") (pintype "passive"))
    )
    (net (code "151") (name "Net-(R150-Pad2)") (class "Default")
      (node (ref "R150") (pin "2") (pinfunction "2_2") (pintype "passive"))
      (node (ref "U19") (pin "19") (pinfunction "19_19") (pintype "passive"))
    )
    (net (code "152") (name "Net-(R151-Pad2)") (class "Default")
      (node (ref "R151") (pin "2") (pinfunction "2_2") (pintype "passive"))
      (node (ref "U20") (pin "1") (pinfunction "1_1") (pintype "passive"))
    )
    (net (code "153") (name "Net-(R152-Pad2)") (class "Default")
      (node (ref "R152") (pin "2") (pinfunction "2_2") (pintype "passive"))
      (node (ref "U20") (pin "3") (pinfunction "3_3") (pintype "passive"))
    )
    (net (code "154") (name "Net-(R153-Pad2)") (class "Default")
      (node (ref "R153") (pin "2") (pinfunction "2_2") (pintype "passive"))
      (node (ref "U20") (pin "5") (pinfunction "5_5") (pintype "passive"))
    )
    (net (code "155") (name "Net-(R154-Pad2)") (class "Default")
      (node (ref "R154") (pin "2") (pinfunction "2_2") (pintype "passive"))
      (node (ref "U20") (pin "7") (pinfunction "7_7") (pintype "passive"))
    )
    (net (code "156") (name "Net-(R155-Pad2)") (class "Default")
      (node (ref "R155") (pin "2") (pinfunction "2_2") (pintype "passive"))
      (node (ref "U20") (pin "9") (pinfunction "9_9") (pintype "passive"))
    )
    (net (code "157") (name "Net-(R156-Pad2)") (class "Default")
      (node (ref "R156") (pin "2") (pinfunction "2_2") (pintype "passive"))
      (node (ref "U20") (pin "11") (pinfunction "11_11") (pintype "passive"))
    )
    (net (code "158") (name "Net-(R157-Pad2)") (class "Default")
      (node (ref "R157") (pin "2") (pinfunction "2_2") (pintype "passive"))
      (node (ref "U20") (pin "13") (pinfunction "13_13") (pintype "passive"))
    )
    (net (code "159") (name "Net-(R158-Pad2)") (class "Default")
      (node (ref "R158") (pin "2") (pinfunction "2_2") (pintype "passive"))
      (node (ref "U20") (pin "15") (pinfunction "15_15") (pintype "passive"))
    )
    (net (code "160") (name "Net-(R159-Pad2)") (class "Default")
      (node (ref "R159") (pin "2") (pinfunction "2_2") (pintype "passive"))
      (node (ref "U20") (pin "17") (pinfunction "17_17") (pintype "passive"))
    )
    (net (code "161") (name "Net-(R160-Pad2)") (class "Default")
      (node (ref "R160") (pin "2") (pinfunction "2_2") (pintype "passive"))
      (node (ref "U20") (pin "19") (pinfunction "19_19") (pintype "passive"))
    )
    (net (code "162") (name "Net-(U1-GP0_SPI0RX_I2C0SDA_UART0TX)") (class "Default")
      (node (ref "U1") (pin "1") (pinfunction "GP0_SPI0RX_I2C0SDA_UART0TX_1") (pintype "passive"))
      (node (ref "U9") (pin "1") (pinfunction "IN1_1") (pintype "passive"))
    )
    (net (code "163") (name "Net-(U1-GP1_SPI0CSn_I2C0SCL_UART0RX)") (class "Default")
      (node (ref "U1") (pin "2") (pinfunction "GP1_SPI0CSn_I2C0SCL_UART0RX_2") (pintype "passive"))
      (node (ref "U9") (pin "3") (pinfunction "IN3_3") (pintype "passive"))
    )
    (net (code "164") (name "Net-(U1-GP2_SPI0SCK_I2C1SDA)") (class "Default")
      (node (ref "U1") (pin "4") (pinfunction "GP2_SPI0SCK_I2C1SDA_4") (pintype "passive"))
      (node (ref "U9") (pin "5") (pinfunction "IN5_5") (pintype "passive"))
    )
    (net (code "165") (name "Net-(U1-GP3_SPI0TX_I2C1SCL)") (class "Default")
      (node (ref "U1") (pin "5") (pinfunction "GP3_SPI0TX_I2C1SCL_5") (pintype "passive"))
      (node (ref "U9") (pin "7") (pinfunction "IN7_7") (pintype "passive"))
    )
    (net (code "166") (name "Net-(U1-GP4_SPI0RX_I2C0SDA_UART1TX)") (class "Default")
      (node (ref "U1") (pin "6") (pinfunction "GP4_SPI0RX_I2C0SDA_UART1TX_6") (pintype "passive"))
      (node (ref "U18") (pin "1") (pinfunction "IN1_1") (pintype "passive"))
    )
    (net (code "167") (name "Net-(U1-GP5_SPI0CSn_I2C0SCL_UART1RX)") (class "Default")
      (node (ref "U1") (pin "7") (pinfunction "GP5_SPI0CSn_I2C0SCL_UART1RX_7") (pintype "passive"))
      (node (ref "U18") (pin "3") (pinfunction "IN3_3") (pintype "passive"))
    )
    (net (code "168") (name "Net-(U1-GP6_SPI0SCK_I2C1SDA)") (class "Default")
      (node (ref "U1") (pin "9") (pinfunction "GP6_SPI0SCK_I2C1SDA_9") (pintype "passive"))
      (node (ref "U18") (pin "5") (pinfunction "IN5_5") (pintype "passive"))
    )
    (net (code "169") (name "Net-(U1-GP7_SPI0TX_I2C1SCL)") (class "Default")
      (node (ref "U1") (pin "10") (pinfunction "GP7_SPI0TX_I2C1SCL_10") (pintype "passive"))
      (node (ref "U18") (pin "7") (pinfunction "IN7_7") (pintype "passive"))
    )
    (net (code "170") (name "Net-(U1-GP8_SPI1RX_I2C0SDA_UART1TX)") (class "Default")
      (node (ref "U1") (pin "11") (pinfunction "GP8_SPI1RX_I2C0SDA_UART1TX_11") (pintype "passive"))
      (node (ref "U23") (pin "1") (pinfunction "IN1_1") (pintype "passive"))
    )
    (net (code "171") (name "Net-(U1-GP9_SPI1CSn_I2C0SCL_UART1RX)") (class "Default")
      (node (ref "U1") (pin "12") (pinfunction "GP9_SPI1CSn_I2C0SCL_UART1RX_12") (pintype "passive"))
      (node (ref "U23") (pin "3") (pinfunction "IN3_3") (pintype "passive"))
    )
    (net (code "172") (name "Net-(U1-GP10_SPI1SCK_I2C1SDA)") (class "Default")
      (node (ref "U1") (pin "14") (pinfunction "GP10_SPI1SCK_I2C1SDA_14") (pintype "passive"))
      (node (ref "U23") (pin "5") (pinfunction "IN5_5") (pintype "passive"))
    )
    (net (code "173") (name "Net-(U1-GP11_SPI1TX_I2C1SCL)") (class "Default")
      (node (ref "U1") (pin "15") (pinfunction "GP11_SPI1TX_I2C1SCL_15") (pintype "passive"))
      (node (ref "U23") (pin "7") (pinfunction "IN7_7") (pintype "passive"))
    )
    (net (code "174") (name "Net-(U1-GP12_SPI1RX_I2C0SDA_UART0TX)") (class "Default")
      (node (ref "U1") (pin "16") (pinfunction "GP12_SPI1RX_I2C0SDA_UART0TX_16") (pintype "passive"))
      (node (ref "U8") (pin "1") (pinfunction "IN1_1") (pintype "passive"))
    )
    (net (code "175") (name "Net-(U1-GP13_SPI1CSn_I2C0SCL_UART0RX)") (class "Default")
      (node (ref "U1") (pin "17") (pinfunction "GP13_SPI1CSn_I2C0SCL_UART0RX_17") (pintype "passive"))
      (node (ref "U8") (pin "3") (pinfunction "IN3_3") (pintype "passive"))
    )
    (net (code "176") (name "Net-(U1-GP14_SPI1SCK_I2C1SDA)") (class "Default")
      (node (ref "U1") (pin "19") (pinfunction "GP14_SPI1SCK_I2C1SDA_19") (pintype "passive"))
      (node (ref "U8") (pin "5") (pinfunction "IN5_5") (pintype "passive"))
    )
    (net (code "177") (name "Net-(U1-GP15_SPI1TX_I2C1SCL)") (class "Default")
      (node (ref "U1") (pin "20") (pinfunction "GP15_SPI1TX_I2C1SCL_20") (pintype "passive"))
      (node (ref "U8") (pin "7") (pinfunction "IN7_7") (pintype "passive"))
    )
    (net (code "178") (name "Net-(U2-Pad10)") (class "Default")
      (node (ref "U2") (pin "10") (pinfunction "10_10") (pintype "passive"))
      (node (ref "U2") (pin "12") (pinfunction "12_12") (pintype "passive"))
      (node (ref "U2") (pin "14") (pinfunction "14_14") (pintype "passive"))
      (node (ref "U2") (pin "16") (pinfunction "16_16") (pintype "passive"))
      (node (ref "U2") (pin "18") (pinfunction "18_18") (pintype "passive"))
      (node (ref "U2") (pin "2") (pinfunction "2_2") (pintype "passive"))
      (node (ref "U2") (pin "20") (pinfunction "20_20") (pintype "passive"))
      (node (ref "U2") (pin "4") (pinfunction "4_4") (pintype "passive"))
      (node (ref "U2") (pin "6") (pinfunction "6_6") (pintype "passive"))
      (node (ref "U2") (pin "8") (pinfunction "8_8") (pintype "passive"))
      (node (ref "U22") (pin "15") (pinfunction "15_15") (pintype "passive"))
    )
    (net (code "179") (name "Net-(U8-OUT1)") (class "Default")
      (node (ref "R10") (pin "1") (pinfunction "1_1") (pintype "passive"))
      (node (ref "R11") (pin "1") (pinfunction "1_1") (pintype "passive"))
      (node (ref "R2") (pin "1") (pinfunction "1_1") (pintype "passive"))
      (node (ref "R3") (pin "1") (pinfunction "1_1") (pintype "passive"))
      (node (ref "R4") (pin "1") (pinfunction "1_1") (pintype "passive"))
      (node (ref "R5") (pin "1") (pinfunction "1_1") (pintype "passive"))
      (node (ref "R6") (pin "1") (pinfunction "1_1") (pintype "passive"))
      (node (ref "R7") (pin "1") (pinfunction "1_1") (pintype "passive"))
      (node (ref "R8") (pin "1") (pinfunction "1_1") (pintype "passive"))
      (node (ref "R9") (pin "1") (pinfunction "1_1") (pintype "passive"))
      (node (ref "U8") (pin "16") (pinfunction "OUT1_16") (pintype "passive"))
    )
    (net (code "180") (name "Net-(U8-OUT3)") (class "Default")
      (node (ref "R12") (pin "1") (pinfunction "1_1") (pintype "passive"))
      (node (ref "R13") (pin "1") (pinfunction "1_1") (pintype "passive"))
      (node (ref "R14") (pin "1") (pinfunction "1_1") (pintype "passive"))
      (node (ref "R15") (pin "1") (pinfunction "1_1") (pintype "passive"))
      (node (ref "R16") (pin "1") (pinfunction "1_1") (pintype "passive"))
      (node (ref "R17") (pin "1") (pinfunction "1_1") (pintype "passive"))
      (node (ref "R18") (pin "1") (pinfunction "1_1") (pintype "passive"))
      (node (ref "R19") (pin "1") (pinfunction "1_1") (pintype "passive"))
      (node (ref "R20") (pin "1") (pinfunction "1_1") (pintype "passive"))
      (node (ref "R21") (pin "1") (pinfunction "1_1") (pintype "passive"))
      (node (ref "U8") (pin "14") (pinfunction "OUT3_14") (pintype "passive"))
    )
    (net (code "181") (name "Net-(U8-OUT5)") (class "Default")
      (node (ref "R22") (pin "1") (pinfunction "1_1") (pintype "passive"))
      (node (ref "R23") (pin "1") (pinfunction "1_1") (pintype "passive"))
      (node (ref "R24") (pin "1") (pinfunction "1_1") (pintype "passive"))
      (node (ref "R25") (pin "1") (pinfunction "1_1") (pintype "passive"))
      (node (ref "R26") (pin "1") (pinfunction "1_1") (pintype "passive"))
      (node (ref "R27") (pin "1") (pinfunction "1_1") (pintype "passive"))
      (node (ref "R28") (pin "1") (pinfunction "1_1") (pintype "passive"))
      (node (ref "R29") (pin "1") (pinfunction "1_1") (pintype "passive"))
      (node (ref "R30") (pin "1") (pinfunction "1_1") (pintype "passive"))
      (node (ref "R31") (pin "1") (pinfunction "1_1") (pintype "passive"))
      (node (ref "U8") (pin "12") (pinfunction "OUT5_12") (pintype "passive"))
    )
    (net (code "182") (name "Net-(U8-OUT7)") (class "Default")
      (node (ref "R33") (pin "1") (pinfunction "1_1") (pintype "passive"))
      (node (ref "R34") (pin "1") (pinfunction "1_1") (pintype "passive"))
      (node (ref "R35") (pin "1") (pinfunction "1_1") (pintype "passive"))
      (node (ref "R36") (pin "1") (pinfunction "1_1") (pintype "passive"))
      (node (ref "R37") (pin "1") (pinfunction "1_1") (pintype "passive"))
      (node (ref "R38") (pin "1") (pinfunction "1_1") (pintype "passive"))
      (node (ref "R39") (pin "1") (pinfunction "1_1") (pintype "passive"))
      (node (ref "R40") (pin "1") (pinfunction "1_1") (pintype "passive"))
      (node (ref "R41") (pin "1") (pinfunction "1_1") (pintype "passive"))
      (node (ref "R42") (pin "1") (pinfunction "1_1") (pintype "passive"))
      (node (ref "U8") (pin "10") (pinfunction "OUT7_10") (pintype "passive"))
    )
    (net (code "183") (name "Net-(U9-OUT1)") (class "Default")
      (node (ref "R1") (pin "1") (pinfunction "1_1") (pintype "passive"))
      (node (ref "R32") (pin "1") (pinfunction "1_1") (pintype "passive"))
      (node (ref "R63") (pin "1") (pinfunction "1_1") (pintype "passive"))
      (node (ref "R64") (pin "1") (pinfunction "1_1") (pintype "passive"))
      (node (ref "R65") (pin "1") (pinfunction "1_1") (pintype "passive"))
      (node (ref "R66") (pin "1") (pinfunction "1_1") (pintype "passive"))
      (node (ref "R67") (pin "1") (pinfunction "1_1") (pintype "passive"))
      (node (ref "R68") (pin "1") (pinfunction "1_1") (pintype "passive"))
      (node (ref "R69") (pin "1") (pinfunction "1_1") (pintype "passive"))
      (node (ref "R70") (pin "1") (pinfunction "1_1") (pintype "passive"))
      (node (ref "U9") (pin "16") (pinfunction "OUT1_16") (pintype "passive"))
    )
    (net (code "184") (name "Net-(U9-OUT3)") (class "Default")
      (node (ref "R71") (pin "1") (pinfunction "1_1") (pintype "passive"))
      (node (ref "R72") (pin "1") (pinfunction "1_1") (pintype "passive"))
      (node (ref "R73") (pin "1") (pinfunction "1_1") (pintype "passive"))
      (node (ref "R74") (pin "1") (pinfunction "1_1") (pintype "passive"))
      (node (ref "R75") (pin "1") (pinfunction "1_1") (pintype "passive"))
      (node (ref "R76") (pin "1") (pinfunction "1_1") (pintype "passive"))
      (node (ref "R77") (pin "1") (pinfunction "1_1") (pintype "passive"))
      (node (ref "R78") (pin "1") (pinfunction "1_1") (pintype "passive"))
      (node (ref "R79") (pin "1") (pinfunction "1_1") (pintype "passive"))
      (node (ref "R80") (pin "1") (pinfunction "1_1") (pintype "passive"))
      (node (ref "U9") (pin "14") (pinfunction "OUT3_14") (pintype "passive"))
    )
    (net (code "185") (name "Net-(U9-OUT5)") (class "Default")
      (node (ref "R81") (pin "1") (pinfunction "1_1") (pintype "passive"))
      (node (ref "R82") (pin "1") (pinfunction "1_1") (pintype "passive"))
      (node (ref "R83") (pin "1") (pinfunction "1_1") (pintype "passive"))
      (node (ref "R84") (pin "1") (pinfunction "1_1") (pintype "passive"))
      (node (ref "R85") (pin "1") (pinfunction "1_1") (pintype "passive"))
      (node (ref "R86") (pin "1") (pinfunction "1_1") (pintype "passive"))
      (node (ref "R87") (pin "1") (pinfunction "1_1") (pintype "passive"))
      (node (ref "R88") (pin "1") (pinfunction "1_1") (pintype "passive"))
      (node (ref "R89") (pin "1") (pinfunction "1_1") (pintype "passive"))
      (node (ref "R90") (pin "1") (pinfunction "1_1") (pintype "passive"))
      (node (ref "U9") (pin "12") (pinfunction "OUT5_12") (pintype "passive"))
    )
    (net (code "186") (name "Net-(U9-OUT7)") (class "Default")
      (node (ref "R100") (pin "1") (pinfunction "1_1") (pintype "passive"))
      (node (ref "R91") (pin "1") (pinfunction "1_1") (pintype "passive"))
      (node (ref "R92") (pin "1") (pinfunction "1_1") (pintype "passive"))
      (node (ref "R93") (pin "1") (pinfunction "1_1") (pintype "passive"))
      (node (ref "R94") (pin "1") (pinfunction "1_1") (pintype "passive"))
      (node (ref "R95") (pin "1") (pinfunction "1_1") (pintype "passive"))
      (node (ref "R96") (pin "1") (pinfunction "1_1") (pintype "passive"))
      (node (ref "R97") (pin "1") (pinfunction "1_1") (pintype "passive"))
      (node (ref "R98") (pin "1") (pinfunction "1_1") (pintype "passive"))
      (node (ref "R99") (pin "1") (pinfunction "1_1") (pintype "passive"))
      (node (ref "U9") (pin "10") (pinfunction "OUT7_10") (pintype "passive"))
    )
    (net (code "187") (name "Net-(U10-Pad10)") (class "Default")
      (node (ref "U10") (pin "10") (pinfunction "10_10") (pintype "passive"))
      (node (ref "U10") (pin "12") (pinfunction "12_12") (pintype "passive"))
      (node (ref "U10") (pin "14") (pinfunction "14_14") (pintype "passive"))
      (node (ref "U10") (pin "16") (pinfunction "16_16") (pintype "passive"))
      (node (ref "U10") (pin "18") (pinfunction "18_18") (pintype "passive"))
      (node (ref "U10") (pin "2") (pinfunction "2_2") (pintype "passive"))
      (node (ref "U10") (pin "20") (pinfunction "20_20") (pintype "passive"))
      (node (ref "U10") (pin "4") (pinfunction "4_4") (pintype "passive"))
      (node (ref "U10") (pin "6") (pinfunction "6_6") (pintype "passive"))
      (node (ref "U10") (pin "8") (pinfunction "8_8") (pintype "passive"))
      (node (ref "U22") (pin "16") (pinfunction "16_16") (pintype "passive"))
    )
    (net (code "188") (name "Net-(U11-Pad10)") (class "Default")
      (node (ref "U11") (pin "10") (pinfunction "10_10") (pintype "passive"))
      (node (ref "U11") (pin "12") (pinfunction "12_12") (pintype "passive"))
      (node (ref "U11") (pin "14") (pinfunction "14_14") (pintype "passive"))
      (node (ref "U11") (pin "16") (pinfunction "16_16") (pintype "passive"))
      (node (ref "U11") (pin "18") (pinfunction "18_18") (pintype "passive"))
      (node (ref "U11") (pin "2") (pinfunction "2_2") (pintype "passive"))
      (node (ref "U11") (pin "20") (pinfunction "20_20") (pintype "passive"))
      (node (ref "U11") (pin "4") (pinfunction "4_4") (pintype "passive"))
      (node (ref "U11") (pin "6") (pinfunction "6_6") (pintype "passive"))
      (node (ref "U11") (pin "8") (pinfunction "8_8") (pintype "passive"))
      (node (ref "U22") (pin "14") (pinfunction "14_14") (pintype "passive"))
    )
    (net (code "189") (name "Net-(U12-Pad10)") (class "Default")
      (node (ref "U12") (pin "10") (pinfunction "10_10") (pintype "passive"))
      (node (ref "U12") (pin "12") (pinfunction "12_12") (pintype "passive"))
      (node (ref "U12") (pin "14") (pinfunction "14_14") (pintype "passive"))
      (node (ref "U12") (pin "16") (pinfunction "16_16") (pintype "passive"))
      (node (ref "U12") (pin "18") (pinfunction "18_18") (pintype "passive"))
      (node (ref "U12") (pin "2") (pinfunction "2_2") (pintype "passive"))
      (node (ref "U12") (pin "20") (pinfunction "20_20") (pintype "passive"))
      (node (ref "U12") (pin "4") (pinfunction "4_4") (pintype "passive"))
      (node (ref "U12") (pin "6") (pinfunction "6_6") (pintype "passive"))
      (node (ref "U12") (pin "8") (pinfunction "8_8") (pintype "passive"))
      (node (ref "U22") (pin "12") (pinfunction "12_12") (pintype "passive"))
    )
    (net (code "190") (name "Net-(U13-Pad10)") (class "Default")
      (node (ref "U13") (pin "10") (pinfunction "10_10") (pintype "passive"))
      (node (ref "U13") (pin "12") (pinfunction "12_12") (pintype "passive"))
      (node (ref "U13") (pin "14") (pinfunction "14_14") (pintype "passive"))
      (node (ref "U13") (pin "16") (pinfunction "16_16") (pintype "passive"))
      (node (ref "U13") (pin "18") (pinfunction "18_18") (pintype "passive"))
      (node (ref "U13") (pin "2") (pinfunction "2_2") (pintype "passive"))
      (node (ref "U13") (pin "20") (pinfunction "20_20") (pintype "passive"))
      (node (ref "U13") (pin "4") (pinfunction "4_4") (pintype "passive"))
      (node (ref "U13") (pin "6") (pinfunction "6_6") (pintype "passive"))
      (node (ref "U13") (pin "8") (pinfunction "8_8") (pintype "passive"))
      (node (ref "U22") (pin "10") (pinfunction "10_10") (pintype "passive"))
    )
    (net (code "191") (name "Net-(U14-Pad10)") (class "Default")
      (node (ref "U14") (pin "10") (pinfunction "10_10") (pintype "passive"))
      (node (ref "U14") (pin "12") (pinfunction "12_12") (pintype "passive"))
      (node (ref "U14") (pin "14") (pinfunction "14_14") (pintype "passive"))
      (node (ref "U14") (pin "16") (pinfunction "16_16") (pintype "passive"))
      (node (ref "U14") (pin "18") (pinfunction "18_18") (pintype "passive"))
      (node (ref "U14") (pin "2") (pinfunction "2_2") (pintype "passive"))
      (node (ref "U14") (pin "20") (pinfunction "20_20") (pintype "passive"))
      (node (ref "U14") (pin "4") (pinfunction "4_4") (pintype "passive"))
      (node (ref "U14") (pin "6") (pinfunction "6_6") (pintype "passive"))
      (node (ref "U14") (pin "8") (pinfunction "8_8") (pintype "passive"))
      (node (ref "U22") (pin "8") (pinfunction "8_8") (pintype "passive"))
    )
    (net (code "192") (name "Net-(U15-Pad10)") (class "Default")
      (node (ref "U15") (pin "10") (pinfunction "10_10") (pintype "passive"))
      (node (ref "U15") (pin "12") (pinfunction "12_12") (pintype "passive"))
      (node (ref "U15") (pin "14") (pinfunction "14_14") (pintype "passive"))
      (node (ref "U15") (pin "16") (pinfunction "16_16") (pintype "passive"))
      (node (ref "U15") (pin "18") (pinfunction "18_18") (pintype "passive"))
      (node (ref "U15") (pin "2") (pinfunction "2_2") (pintype "passive"))
      (node (ref "U15") (pin "20") (pinfunction "20_20") (pintype "passive"))
      (node (ref "U15") (pin "4") (pinfunction "4_4") (pintype "passive"))
      (node (ref "U15") (pin "6") (pinfunction "6_6") (pintype "passive"))
      (node (ref "U15") (pin "8") (pinfunction "8_8") (pintype "passive"))
      (node (ref "U22") (pin "6") (pinfunction "6_6") (pintype "passive"))
    )
    (net (code "193") (name "Net-(U16-Pad10)") (class "Default")
      (node (ref "U16") (pin "10") (pinfunction "10_10") (pintype "passive"))
      (node (ref "U16") (pin "12") (pinfunction "12_12") (pintype "passive"))
      (node (ref "U16") (pin "14") (pinfunction "14_14") (pintype "passive"))
      (node (ref "U16") (pin "16") (pinfunction "16_16") (pintype "passive"))
      (node (ref "U16") (pin "18") (pinfunction "18_18") (pintype "passive"))
      (node (ref "U16") (pin "2") (pinfunction "2_2") (pintype "passive"))
      (node (ref "U16") (pin "20") (pinfunction "20_20") (pintype "passive"))
      (node (ref "U16") (pin "4") (pinfunction "4_4") (pintype "passive"))
      (node (ref "U16") (pin "6") (pinfunction "6_6") (pintype "passive"))
      (node (ref "U16") (pin "8") (pinfunction "8_8") (pintype "passive"))
      (node (ref "U22") (pin "3") (pinfunction "3_3") (pintype "passive"))
    )
    (net (code "194") (name "Net-(U17-Pad10)") (class "Default")
      (node (ref "U17") (pin "10") (pinfunction "10_10") (pintype "passive"))
      (node (ref "U17") (pin "12") (pinfunction "12_12") (pintype "passive"))
      (node (ref "U17") (pin "14") (pinfunction "14_14") (pintype "passive"))
      (node (ref "U17") (pin "16") (pinfunction "16_16") (pintype "passive"))
      (node (ref "U17") (pin "18") (pinfunction "18_18") (pintype "passive"))
      (node (ref "U17") (pin "2") (pinfunction "2_2") (pintype "passive"))
      (node (ref "U17") (pin "20") (pinfunction "20_20") (pintype "passive"))
      (node (ref "U17") (pin "4") (pinfunction "4_4") (pintype "passive"))
      (node (ref "U17") (pin "6") (pinfunction "6_6") (pintype "passive"))
      (node (ref "U17") (pin "8") (pinfunction "8_8") (pintype "passive"))
      (node (ref "U22") (pin "4") (pinfunction "4_4") (pintype "passive"))
    )
    (net (code "195") (name "Net-(U18-OUT1)") (class "Default")
      (node (ref "R101") (pin "1") (pinfunction "1_1") (pintype "passive"))
      (node (ref "R102") (pin "1") (pinfunction "1_1") (pintype "passive"))
      (node (ref "R103") (pin "1") (pinfunction "1_1") (pintype "passive"))
      (node (ref "R104") (pin "1") (pinfunction "1_1") (pintype "passive"))
      (node (ref "R105") (pin "1") (pinfunction "1_1") (pintype "passive"))
      (node (ref "R106") (pin "1") (pinfunction "1_1") (pintype "passive"))
      (node (ref "R107") (pin "1") (pinfunction "1_1") (pintype "passive"))
      (node (ref "R108") (pin "1") (pinfunction "1_1") (pintype "passive"))
      (node (ref "R109") (pin "1") (pinfunction "1_1") (pintype "passive"))
      (node (ref "R110") (pin "1") (pinfunction "1_1") (pintype "passive"))
      (node (ref "U18") (pin "16") (pinfunction "OUT1_16") (pintype "passive"))
    )
    (net (code "196") (name "Net-(U18-OUT3)") (class "Default")
      (node (ref "R111") (pin "1") (pinfunction "1_1") (pintype "passive"))
      (node (ref "R112") (pin "1") (pinfunction "1_1") (pintype "passive"))
      (node (ref "R113") (pin "1") (pinfunction "1_1") (pintype "passive"))
      (node (ref "R114") (pin "1") (pinfunction "1_1") (pintype "passive"))
      (node (ref "R115") (pin "1") (pinfunction "1_1") (pintype "passive"))
      (node (ref "R116") (pin "1") (pinfunction "1_1") (pintype "passive"))
      (node (ref "R117") (pin "1") (pinfunction "1_1") (pintype "passive"))
      (node (ref "R118") (pin "1") (pinfunction "1_1") (pintype "passive"))
      (node (ref "R119") (pin "1") (pinfunction "1_1") (pintype "passive"))
      (node (ref "R120") (pin "1") (pinfunction "1_1") (pintype "passive"))
      (node (ref "U18") (pin "14") (pinfunction "OUT3_14") (pintype "passive"))
    )
    (net (code "197") (name "Net-(U18-OUT5)") (class "Default")
      (node (ref "R131") (pin "1") (pinfunction "1_1") (pintype "passive"))
      (node (ref "R132") (pin "1") (pinfunction "1_1") (pintype "passive"))
      (node (ref "R133") (pin "1") (pinfunction "1_1") (pintype "passive"))
      (node (ref "R134") (pin "1") (pinfunction "1_1") (pintype "passive"))
      (node (ref "R135") (pin "1") (pinfunction "1_1") (pintype "passive"))
      (node (ref "R136") (pin "1") (pinfunction "1_1") (pintype "passive"))
      (node (ref "R137") (pin "1") (pinfunction "1_1") (pintype "passive"))
      (node (ref "R138") (pin "1") (pinfunction "1_1") (pintype "passive"))
      (node (ref "R139") (pin "1") (pinfunction "1_1") (pintype "passive"))
      (node (ref "R140") (pin "1") (pinfunction "1_1") (pintype "passive"))
      (node (ref "U18") (pin "12") (pinfunction "OUT5_12") (pintype "passive"))
    )
    (net (code "198") (name "Net-(U18-OUT7)") (class "Default")
      (node (ref "R151") (pin "1") (pinfunction "1_1") (pintype "passive"))
      (node (ref "R152") (pin "1") (pinfunction "1_1") (pintype "passive"))
      (node (ref "R153") (pin "1") (pinfunction "1_1") (pintype "passive"))
      (node (ref "R154") (pin "1") (pinfunction "1_1") (pintype "passive"))
      (node (ref "R155") (pin "1") (pinfunction "1_1") (pintype "passive"))
      (node (ref "R156") (pin "1") (pinfunction "1_1") (pintype "passive"))
      (node (ref "R157") (pin "1") (pinfunction "1_1") (pintype "passive"))
      (node (ref "R158") (pin "1") (pinfunction "1_1") (pintype "passive"))
      (node (ref "R159") (pin "1") (pinfunction "1_1") (pintype "passive"))
      (node (ref "R160") (pin "1") (pinfunction "1_1") (pintype "passive"))
      (node (ref "U18") (pin "10") (pinfunction "OUT7_10") (pintype "passive"))
    )
    (net (code "199") (name "Net-(U19-Pad10)") (class "Default")
      (node (ref "U19") (pin "10") (pinfunction "10_10") (pintype "passive"))
      (node (ref "U19") (pin "12") (pinfunction "12_12") (pintype "passive"))
      (node (ref "U19") (pin "14") (pinfunction "14_14") (pintype "passive"))
      (node (ref "U19") (pin "16") (pinfunction "16_16") (pintype "passive"))
      (node (ref "U19") (pin "18") (pinfunction "18_18") (pintype "passive"))
      (node (ref "U19") (pin "2") (pinfunction "2_2") (pintype "passive"))
      (node (ref "U19") (pin "20") (pinfunction "20_20") (pintype "passive"))
      (node (ref "U19") (pin "4") (pinfunction "4_4") (pintype "passive"))
      (node (ref "U19") (pin "6") (pinfunction "6_6") (pintype "passive"))
      (node (ref "U19") (pin "8") (pinfunction "8_8") (pintype "passive"))
      (node (ref "U22") (pin "1") (pinfunction "1_1") (pintype "passive"))
    )
    (net (code "200") (name "Net-(U20-Pad10)") (class "Default")
      (node (ref "U20") (pin "10") (pinfunction "10_10") (pintype "passive"))
      (node (ref "U20") (pin "12") (pinfunction "12_12") (pintype "passive"))
      (node (ref "U20") (pin "14") (pinfunction "14_14") (pintype "passive"))
      (node (ref "U20") (pin "16") (pinfunction "16_16") (pintype "passive"))
      (node (ref "U20") (pin "18") (pinfunction "18_18") (pintype "passive"))
      (node (ref "U20") (pin "2") (pinfunction "2_2") (pintype "passive"))
      (node (ref "U20") (pin "20") (pinfunction "20_20") (pintype "passive"))
      (node (ref "U20") (pin "4") (pinfunction "4_4") (pintype "passive"))
      (node (ref "U20") (pin "6") (pinfunction "6_6") (pintype "passive"))
      (node (ref "U20") (pin "8") (pinfunction "8_8") (pintype "passive"))
      (node (ref "U22") (pin "2") (pinfunction "2_2") (pintype "passive"))
    )
    (net (code "201") (name "Net-(U22-Pad5)") (class "Default")
      (node (ref "U22") (pin "5") (pinfunction "5_5") (pintype "passive"))
      (node (ref "U7") (pin "10") (pinfunction "10_10") (pintype "passive"))
      (node (ref "U7") (pin "12") (pinfunction "12_12") (pintype "passive"))
      (node (ref "U7") (pin "14") (pinfunction "14_14") (pintype "passive"))
      (node (ref "U7") (pin "16") (pinfunction "16_16") (pintype "passive"))
      (node (ref "U7") (pin "18") (pinfunction "18_18") (pintype "passive"))
      (node (ref "U7") (pin "2") (pinfunction "2_2") (pintype "passive"))
      (node (ref "U7") (pin "20") (pinfunction "20_20") (pintype "passive"))
      (node (ref "U7") (pin "4") (pinfunction "4_4") (pintype "passive"))
      (node (ref "U7") (pin "6") (pinfunction "6_6") (pintype "passive"))
      (node (ref "U7") (pin "8") (pinfunction "8_8") (pintype "passive"))
    )
    (net (code "202") (name "Net-(U22-Pad7)") (class "Default")
      (node (ref "U22") (pin "7") (pinfunction "7_7") (pintype "passive"))
      (node (ref "U6") (pin "10") (pinfunction "10_10") (pintype "passive"))
      (node (ref "U6") (pin "12") (pinfunction "12_12") (pintype "passive"))
      (node (ref "U6") (pin "14") (pinfunction "14_14") (pintype "passive"))
      (node (ref "U6") (pin "16") (pinfunction "16_16") (pintype "passive"))
      (node (ref "U6") (pin "18") (pinfunction "18_18") (pintype "passive"))
      (node (ref "U6") (pin "2") (pinfunction "2_2") (pintype "passive"))
      (node (ref "U6") (pin "20") (pinfunction "20_20") (pintype "passive"))
      (node (ref "U6") (pin "4") (pinfunction "4_4") (pintype "passive"))
      (node (ref "U6") (pin "6") (pinfunction "6_6") (pintype "passive"))
      (node (ref "U6") (pin "8") (pinfunction "8_8") (pintype "passive"))
    )
    (net (code "203") (name "Net-(U22-Pad9)") (class "Default")
      (node (ref "U22") (pin "9") (pinfunction "9_9") (pintype "passive"))
      (node (ref "U5") (pin "10") (pinfunction "10_10") (pintype "passive"))
      (node (ref "U5") (pin "12") (pinfunction "12_12") (pintype "passive"))
      (node (ref "U5") (pin "14") (pinfunction "14_14") (pintype "passive"))
      (node (ref "U5") (pin "16") (pinfunction "16_16") (pintype "passive"))
      (node (ref "U5") (pin "18") (pinfunction "18_18") (pintype "passive"))
      (node (ref "U5") (pin "2") (pinfunction "2_2") (pintype "passive"))
      (node (ref "U5") (pin "20") (pinfunction "20_20") (pintype "passive"))
      (node (ref "U5") (pin "4") (pinfunction "4_4") (pintype "passive"))
      (node (ref "U5") (pin "6") (pinfunction "6_6") (pintype "passive"))
      (node (ref "U5") (pin "8") (pinfunction "8_8") (pintype "passive"))
    )
    (net (code "204") (name "Net-(U22-Pad11)") (class "Default")
      (node (ref "U22") (pin "11") (pinfunction "11_11") (pintype "passive"))
      (node (ref "U4") (pin "10") (pinfunction "10_10") (pintype "passive"))
      (node (ref "U4") (pin "12") (pinfunction "12_12") (pintype "passive"))
      (node (ref "U4") (pin "14") (pinfunction "14_14") (pintype "passive"))
      (node (ref "U4") (pin "16") (pinfunction "16_16") (pintype "passive"))
      (node (ref "U4") (pin "18") (pinfunction "18_18") (pintype "passive"))
      (node (ref "U4") (pin "2") (pinfunction "2_2") (pintype "passive"))
      (node (ref "U4") (pin "20") (pinfunction "20_20") (pintype "passive"))
      (node (ref "U4") (pin "4") (pinfunction "4_4") (pintype "passive"))
      (node (ref "U4") (pin "6") (pinfunction "6_6") (pintype "passive"))
      (node (ref "U4") (pin "8") (pinfunction "8_8") (pintype "passive"))
    )
    (net (code "205") (name "Net-(U22-Pad13)") (class "Default")
      (node (ref "U22") (pin "13") (pinfunction "13_13") (pintype "passive"))
      (node (ref "U3") (pin "10") (pinfunction "10_10") (pintype "passive"))
      (node (ref "U3") (pin "12") (pinfunction "12_12") (pintype "passive"))
      (node (ref "U3") (pin "14") (pinfunction "14_14") (pintype "passive"))
      (node (ref "U3") (pin "16") (pinfunction "16_16") (pintype "passive"))
      (node (ref "U3") (pin "18") (pinfunction "18_18") (pintype "passive"))
      (node (ref "U3") (pin "2") (pinfunction "2_2") (pintype "passive"))
      (node (ref "U3") (pin "20") (pinfunction "20_20") (pintype "passive"))
      (node (ref "U3") (pin "4") (pinfunction "4_4") (pintype "passive"))
      (node (ref "U3") (pin "6") (pinfunction "6_6") (pintype "passive"))
      (node (ref "U3") (pin "8") (pinfunction "8_8") (pintype "passive"))
    )
    (net (code "206") (name "Net-(U23-OUT1)") (class "Default")
      (node (ref "R43") (pin "1") (pinfunction "1_1") (pintype "passive"))
      (node (ref "R44") (pin "1") (pinfunction "1_1") (pintype "passive"))
      (node (ref "R45") (pin "1") (pinfunction "1_1") (pintype "passive"))
      (node (ref "R46") (pin "1") (pinfunction "1_1") (pintype "passive"))
      (node (ref "R47") (pin "1") (pinfunction "1_1") (pintype "passive"))
      (node (ref "R48") (pin "1") (pinfunction "1_1") (pintype "passive"))
      (node (ref "R49") (pin "1") (pinfunction "1_1") (pintype "passive"))
      (node (ref "R50") (pin "1") (pinfunction "1_1") (pintype "passive"))
      (node (ref "R51") (pin "1") (pinfunction "1_1") (pintype "passive"))
      (node (ref "R52") (pin "1") (pinfunction "1_1") (pintype "passive"))
      (node (ref "U23") (pin "16") (pinfunction "OUT1_16") (pintype "passive"))
    )
    (net (code "207") (name "Net-(U23-OUT3)") (class "Default")
      (node (ref "R53") (pin "1") (pinfunction "1_1") (pintype "passive"))
      (node (ref "R54") (pin "1") (pinfunction "1_1") (pintype "passive"))
      (node (ref "R55") (pin "1") (pinfunction "1_1") (pintype "passive"))
      (node (ref "R56") (pin "1") (pinfunction "1_1") (pintype "passive"))
      (node (ref "R57") (pin "1") (pinfunction "1_1") (pintype "passive"))
      (node (ref "R58") (pin "1") (pinfunction "1_1") (pintype "passive"))
      (node (ref "R59") (pin "1") (pinfunction "1_1") (pintype "passive"))
      (node (ref "R60") (pin "1") (pinfunction "1_1") (pintype "passive"))
      (node (ref "R61") (pin "1") (pinfunction "1_1") (pintype "passive"))
      (node (ref "R62") (pin "1") (pinfunction "1_1") (pintype "passive"))
      (node (ref "U23") (pin "14") (pinfunction "OUT3_14") (pintype "passive"))
    )
    (net (code "208") (name "Net-(U23-OUT5)") (class "Default")
      (node (ref "R121") (pin "1") (pinfunction "1_1") (pintype "passive"))
      (node (ref "R122") (pin "1") (pinfunction "1_1") (pintype "passive"))
      (node (ref "R123") (pin "1") (pinfunction "1_1") (pintype "passive"))
      (node (ref "R124") (pin "1") (pinfunction "1_1") (pintype "passive"))
      (node (ref "R125") (pin "1") (pinfunction "1_1") (pintype "passive"))
      (node (ref "R126") (pin "1") (pinfunction "1_1") (pintype "passive"))
      (node (ref "R127") (pin "1") (pinfunction "1_1") (pintype "passive"))
      (node (ref "R128") (pin "1") (pinfunction "1_1") (pintype "passive"))
      (node (ref "R129") (pin "1") (pinfunction "1_1") (pintype "passive"))
      (node (ref "R130") (pin "1") (pinfunction "1_1") (pintype "passive"))
      (node (ref "U23") (pin "12") (pinfunction "OUT5_12") (pintype "passive"))
    )
    (net (code "209") (name "Net-(U23-OUT7)") (class "Default")
      (node (ref "R141") (pin "1") (pinfunction "1_1") (pintype "passive"))
      (node (ref "R142") (pin "1") (pinfunction "1_1") (pintype "passive"))
      (node (ref "R143") (pin "1") (pinfunction "1_1") (pintype "passive"))
      (node (ref "R144") (pin "1") (pinfunction "1_1") (pintype "passive"))
      (node (ref "R145") (pin "1") (pinfunction "1_1") (pintype "passive"))
      (node (ref "R146") (pin "1") (pinfunction "1_1") (pintype "passive"))
      (node (ref "R147") (pin "1") (pinfunction "1_1") (pintype "passive"))
      (node (ref "R148") (pin "1") (pinfunction "1_1") (pintype "passive"))
      (node (ref "R149") (pin "1") (pinfunction "1_1") (pintype "passive"))
      (node (ref "R150") (pin "1") (pinfunction "1_1") (pintype "passive"))
      (node (ref "U23") (pin "10") (pinfunction "OUT7_10") (pintype "passive"))
    )
    (net (code "210") (name "VCC") (class "Default")
      (node (ref "C3") (pin "1") (pinfunction "1_1") (pintype "passive"))
      (node (ref "U1") (pin "40") (pinfunction "VBUS_40") (pintype "passive"))
      (node (ref "U18") (pin "9") (pinfunction "COM_9") (pintype "passive"))
      (node (ref "U21") (pin "1") (pinfunction "1_1") (pintype "passive"))
      (node (ref "U21") (pin "2") (pinfunction "2_2") (pintype "passive"))
      (node (ref "U23") (pin "9") (pinfunction "COM_9") (pintype "passive"))
      (node (ref "U24") (pin "2") (pinfunction "2_2") (pintype "passive"))
      (node (ref "U25") (pin "1") (pinfunction "1_1") (pintype "passive"))
      (node (ref "U26") (pin "1") (pinfunction "1_1") (pintype "passive"))
      (node (ref "U27") (pin "1") (pinfunction "1_1") (pintype "passive"))
      (node (ref "U28") (pin "1") (pinfunction "1_1") (pintype "passive"))
      (node (ref "U37") (pin "1") (pinfunction "1_1") (pintype "passive"))
      (node (ref "U37") (pin "10") (pinfunction "10_10") (pintype "passive"))
      (node (ref "U37") (pin "11") (pinfunction "11_11") (pintype "passive"))
      (node (ref "U37") (pin "12") (pinfunction "12_12") (pintype "passive"))
      (node (ref "U37") (pin "13") (pinfunction "13_13") (pintype "passive"))
      (node (ref "U37") (pin "14") (pinfunction "14_14") (pintype "passive"))
      (node (ref "U37") (pin "15") (pinfunction "15_15") (pintype "passive"))
      (node (ref "U37") (pin "16") (pinfunction "16_16") (pintype "passive"))
      (node (ref "U37") (pin "2") (pinfunction "2_2") (pintype "passive"))
      (node (ref "U37") (pin "3") (pinfunction "3_3") (pintype "passive"))
      (node (ref "U37") (pin "4") (pinfunction "4_4") (pintype "passive"))
      (node (ref "U37") (pin "5") (pinfunction "5_5") (pintype "passive"))
      (node (ref "U37") (pin "6") (pinfunction "6_6") (pintype "passive"))
      (node (ref "U37") (pin "7") (pinfunction "7_7") (pintype "passive"))
      (node (ref "U37") (pin "8") (pinfunction "8_8") (pintype "passive"))
      (node (ref "U37") (pin "9") (pinfunction "9_9") (pintype "passive"))
      (node (ref "U8") (pin "9") (pinfunction "COM_9") (pintype "passive"))
      (node (ref "U9") (pin "9") (pinfunction "COM_9") (pintype "passive"))
    )
    (net (code "211") (name "unconnected-(U1-3V3(OUT)-Pad36)") (class "Default")
      (node (ref "U1") (pin "36") (pinfunction "3V3(OUT)_36") (pintype "passive"))
    )
    (net (code "212") (name "unconnected-(U1-3V3_EN-Pad37)") (class "Default")
      (node (ref "U1") (pin "37") (pinfunction "3V3_EN_37") (pintype "passive"))
    )
    (net (code "213") (name "unconnected-(U1-ADC_VREF-Pad35)") (class "Default")
      (node (ref "U1") (pin "35") (pinfunction "ADC_VREF_35") (pintype "passive"))
    )
    (net (code "214") (name "unconnected-(U1-GND-Pad3)") (class "Default")
      (node (ref "U1") (pin "3") (pinfunction "GND_3") (pintype "passive"))
    )
    (net (code "215") (name "unconnected-(U1-GND-Pad8)") (class "Default")
      (node (ref "U1") (pin "8") (pinfunction "GND_8") (pintype "passive"))
    )
    (net (code "216") (name "unconnected-(U1-GND-Pad13)") (class "Default")
      (node (ref "U1") (pin "13") (pinfunction "GND_13") (pintype "passive"))
    )
    (net (code "217") (name "unconnected-(U1-GND-Pad18)") (class "Default")
      (node (ref "U1") (pin "18") (pinfunction "GND_18") (pintype "passive"))
    )
    (net (code "218") (name "unconnected-(U1-GND-Pad23)") (class "Default")
      (node (ref "U1") (pin "23") (pinfunction "GND_23") (pintype "passive"))
    )
    (net (code "219") (name "unconnected-(U1-GND-Pad28)") (class "Default")
      (node (ref "U1") (pin "28") (pinfunction "GND_28") (pintype "passive"))
    )
    (net (code "220") (name "unconnected-(U1-GND_AGND-Pad33)") (class "Default")
      (node (ref "U1") (pin "33") (pinfunction "GND_AGND_33") (pintype "passive"))
    )
    (net (code "221") (name "unconnected-(U1-GP16_SPI0RX_UART0RX-Pad21)") (class "Default")
      (node (ref "U1") (pin "21") (pinfunction "GP16_SPI0RX_UART0RX_21") (pintype "passive"))
    )
    (net (code "222") (name "unconnected-(U1-GP17_SPI0CSn_UART0TX-Pad22)") (class "Default")
      (node (ref "U1") (pin "22") (pinfunction "GP17_SPI0CSn_UART0TX_22") (pintype "passive"))
    )
    (net (code "223") (name "unconnected-(U1-GP18_SPI0SCK_I2C1SDA-Pad24)") (class "Default")
      (node (ref "U1") (pin "24") (pinfunction "GP18_SPI0SCK_I2C1SDA_24") (pintype "passive"))
    )
    (net (code "224") (name "unconnected-(U1-GP19_SPI0TX_I2C1SCL-Pad25)") (class "Default")
      (node (ref "U1") (pin "25") (pinfunction "GP19_SPI0TX_I2C1SCL_25") (pintype "passive"))
    )
    (net (code "225") (name "unconnected-(U1-GP20_I2C0SDA-Pad26)") (class "Default")
      (node (ref "U1") (pin "26") (pinfunction "GP20_I2C0SDA_26") (pintype "passive"))
    )
    (net (code "226") (name "unconnected-(U1-GP21_I2C0SCL-Pad27)") (class "Default")
      (node (ref "U1") (pin "27") (pinfunction "GP21_I2C0SCL_27") (pintype "passive"))
    )
    (net (code "227") (name "unconnected-(U1-GP22-Pad29)") (class "Default")
      (node (ref "U1") (pin "29") (pinfunction "GP22_29") (pintype "passive"))
    )
    (net (code "228") (name "unconnected-(U1-GP26_ADC0_I2C1SDA-Pad31)") (class "Default")
      (node (ref "U1") (pin "31") (pinfunction "GP26_ADC0_I2C1SDA_31") (pintype "passive"))
    )
    (net (code "229") (name "unconnected-(U1-GP27_ADC1_I2C1SCL-Pad32)") (class "Default")
      (node (ref "U1") (pin "32") (pinfunction "GP27_ADC1_I2C1SCL_32") (pintype "passive"))
    )
    (net (code "230") (name "unconnected-(U1-GP28_ADC2-Pad34)") (class "Default")
      (node (ref "U1") (pin "34") (pinfunction "GP28_ADC2_34") (pintype "passive"))
    )
    (net (code "231") (name "unconnected-(U1-RUN-Pad30)") (class "Default")
      (node (ref "U1") (pin "30") (pinfunction "RUN_30") (pintype "passive"))
    )
    (net (code "232") (name "unconnected-(U1-VSYS-Pad39)") (class "Default")
      (node (ref "U1") (pin "39") (pinfunction "VSYS_39") (pintype "passive"))
    )
    (net (code "233") (name "unconnected-(U8-IN2-Pad2)") (class "Default")
      (node (ref "U8") (pin "2") (pinfunction "IN2_2") (pintype "passive"))
    )
    (net (code "234") (name "unconnected-(U8-IN4-Pad4)") (class "Default")
      (node (ref "U8") (pin "4") (pinfunction "IN4_4") (pintype "passive"))
    )
    (net (code "235") (name "unconnected-(U8-IN6-Pad6)") (class "Default")
      (node (ref "U8") (pin "6") (pinfunction "IN6_6") (pintype "passive"))
    )
    (net (code "236") (name "unconnected-(U8-OUT2-Pad15)") (class "Default")
      (node (ref "U8") (pin "15") (pinfunction "OUT2_15") (pintype "passive"))
    )
    (net (code "237") (name "unconnected-(U8-OUT4-Pad13)") (class "Default")
      (node (ref "U8") (pin "13") (pinfunction "OUT4_13") (pintype "passive"))
    )
    (net (code "238") (name "unconnected-(U8-OUT6-Pad11)") (class "Default")
      (node (ref "U8") (pin "11") (pinfunction "OUT6_11") (pintype "passive"))
    )
    (net (code "239") (name "unconnected-(U9-IN2-Pad2)") (class "Default")
      (node (ref "U9") (pin "2") (pinfunction "IN2_2") (pintype "passive"))
    )
    (net (code "240") (name "unconnected-(U9-IN4-Pad4)") (class "Default")
      (node (ref "U9") (pin "4") (pinfunction "IN4_4") (pintype "passive"))
    )
    (net (code "241") (name "unconnected-(U9-IN6-Pad6)") (class "Default")
      (node (ref "U9") (pin "6") (pinfunction "IN6_6") (pintype "passive"))
    )
    (net (code "242") (name "unconnected-(U9-OUT2-Pad15)") (class "Default")
      (node (ref "U9") (pin "15") (pinfunction "OUT2_15") (pintype "passive"))
    )
    (net (code "243") (name "unconnected-(U9-OUT4-Pad13)") (class "Default")
      (node (ref "U9") (pin "13") (pinfunction "OUT4_13") (pintype "passive"))
    )
    (net (code "244") (name "unconnected-(U9-OUT6-Pad11)") (class "Default")
      (node (ref "U9") (pin "11") (pinfunction "OUT6_11") (pintype "passive"))
    )
    (net (code "245") (name "unconnected-(U18-IN2-Pad2)") (class "Default")
      (node (ref "U18") (pin "2") (pinfunction "IN2_2") (pintype "passive"))
    )
    (net (code "246") (name "unconnected-(U18-IN4-Pad4)") (class "Default")
      (node (ref "U18") (pin "4") (pinfunction "IN4_4") (pintype "passive"))
    )
    (net (code "247") (name "unconnected-(U18-IN6-Pad6)") (class "Default")
      (node (ref "U18") (pin "6") (pinfunction "IN6_6") (pintype "passive"))
    )
    (net (code "248") (name "unconnected-(U18-OUT2-Pad15)") (class "Default")
      (node (ref "U18") (pin "15") (pinfunction "OUT2_15") (pintype "passive"))
    )
    (net (code "249") (name "unconnected-(U18-OUT4-Pad13)") (class "Default")
      (node (ref "U18") (pin "13") (pinfunction "OUT4_13") (pintype "passive"))
    )
    (net (code "250") (name "unconnected-(U18-OUT6-Pad11)") (class "Default")
      (node (ref "U18") (pin "11") (pinfunction "OUT6_11") (pintype "passive"))
    )
    (net (code "251") (name "unconnected-(U23-IN2-Pad2)") (class "Default")
      (node (ref "U23") (pin "2") (pinfunction "IN2_2") (pintype "passive"))
    )
    (net (code "252") (name "unconnected-(U23-IN4-Pad4)") (class "Default")
      (node (ref "U23") (pin "4") (pinfunction "IN4_4") (pintype "passive"))
    )
    (net (code "253") (name "unconnected-(U23-IN6-Pad6)") (class "Default")
      (node (ref "U23") (pin "6") (pinfunction "IN6_6") (pintype "passive"))
    )
    (net (code "254") (name "unconnected-(U23-OUT2-Pad15)") (class "Default")
      (node (ref "U23") (pin "15") (pinfunction "OUT2_15") (pintype "passive"))
    )
    (net (code "255") (name "unconnected-(U23-OUT4-Pad13)") (class "Default")
      (node (ref "U23") (pin "13") (pinfunction "OUT4_13") (pintype "passive"))
    )
    (net (code "256") (name "unconnected-(U23-OUT6-Pad11)") (class "Default")
      (node (ref "U23") (pin "11") (pinfunction "OUT6_11") (pintype "passive"))
    )
  )
)
